# Microcell_1_4.net
KiCad netlist of a schematic drawn in EAGLE
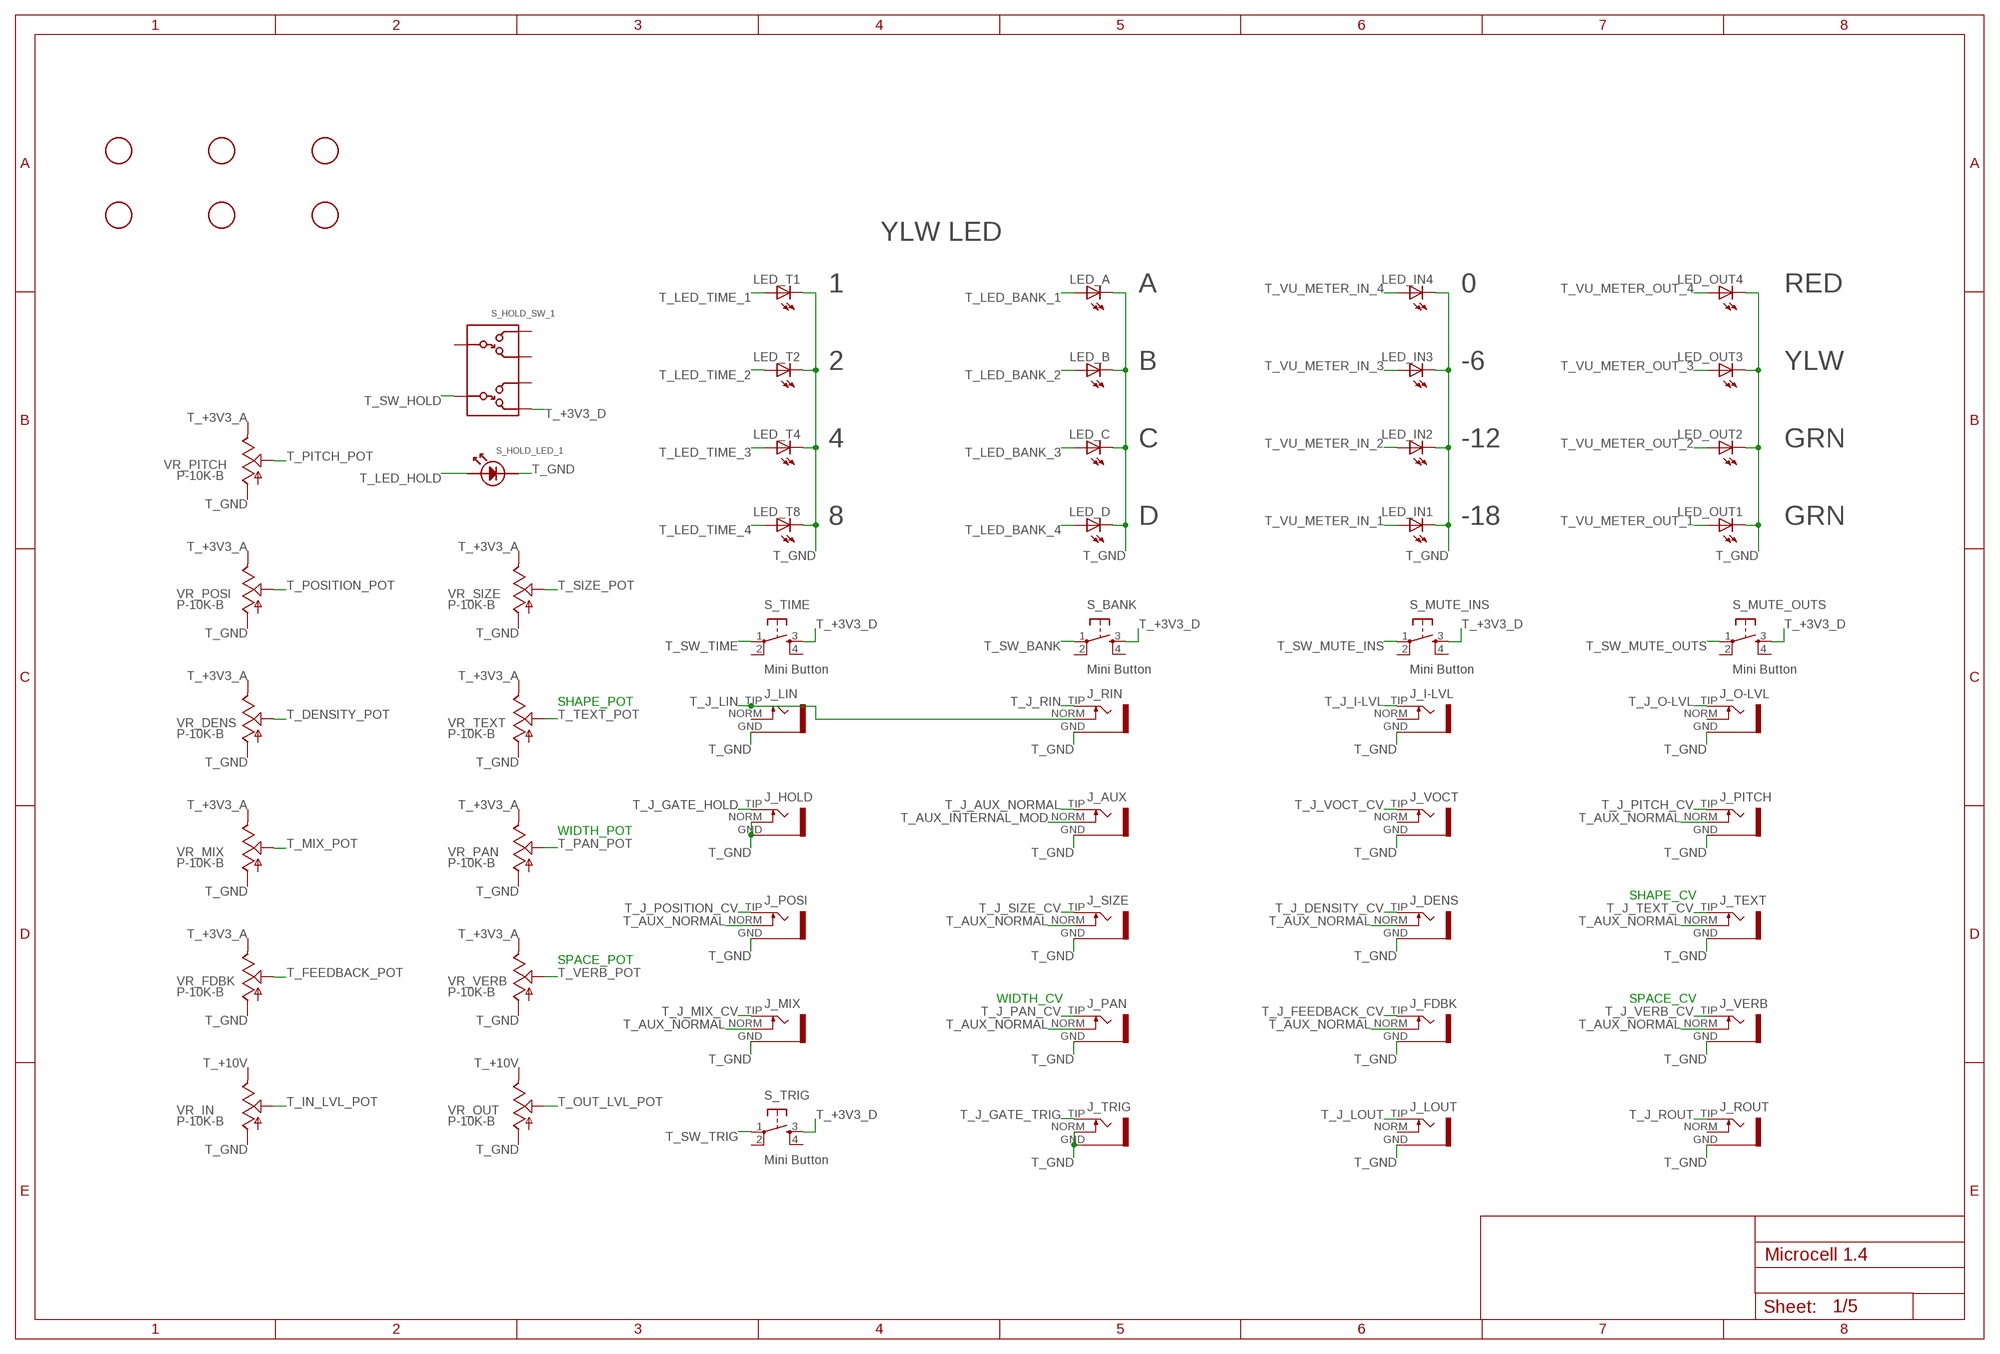
[diagram p0: schematic, sheet 1]
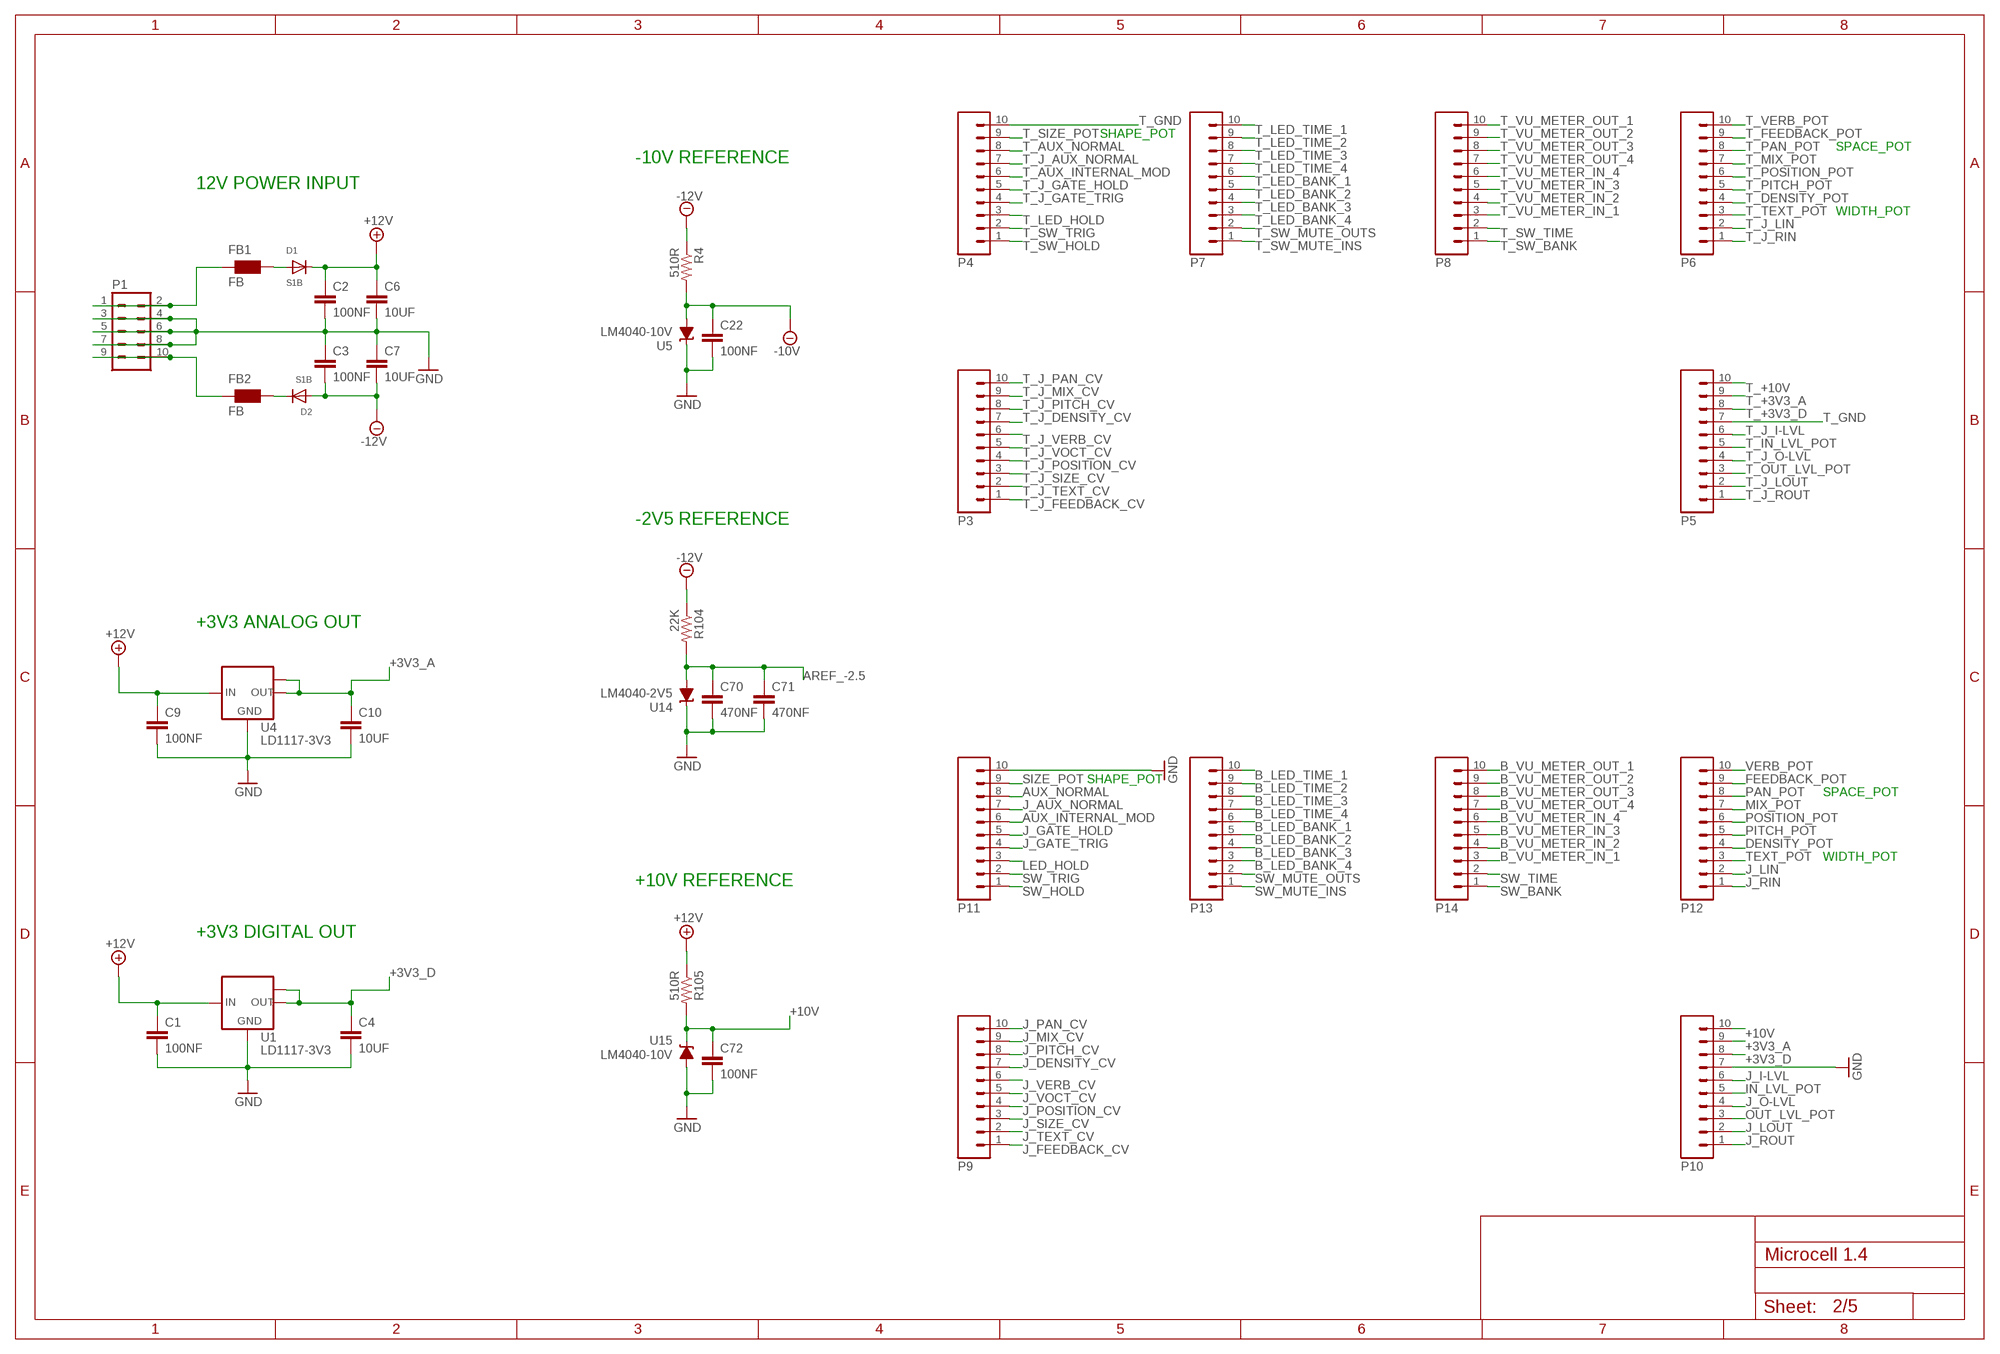
[diagram p1: schematic, sheet 2]
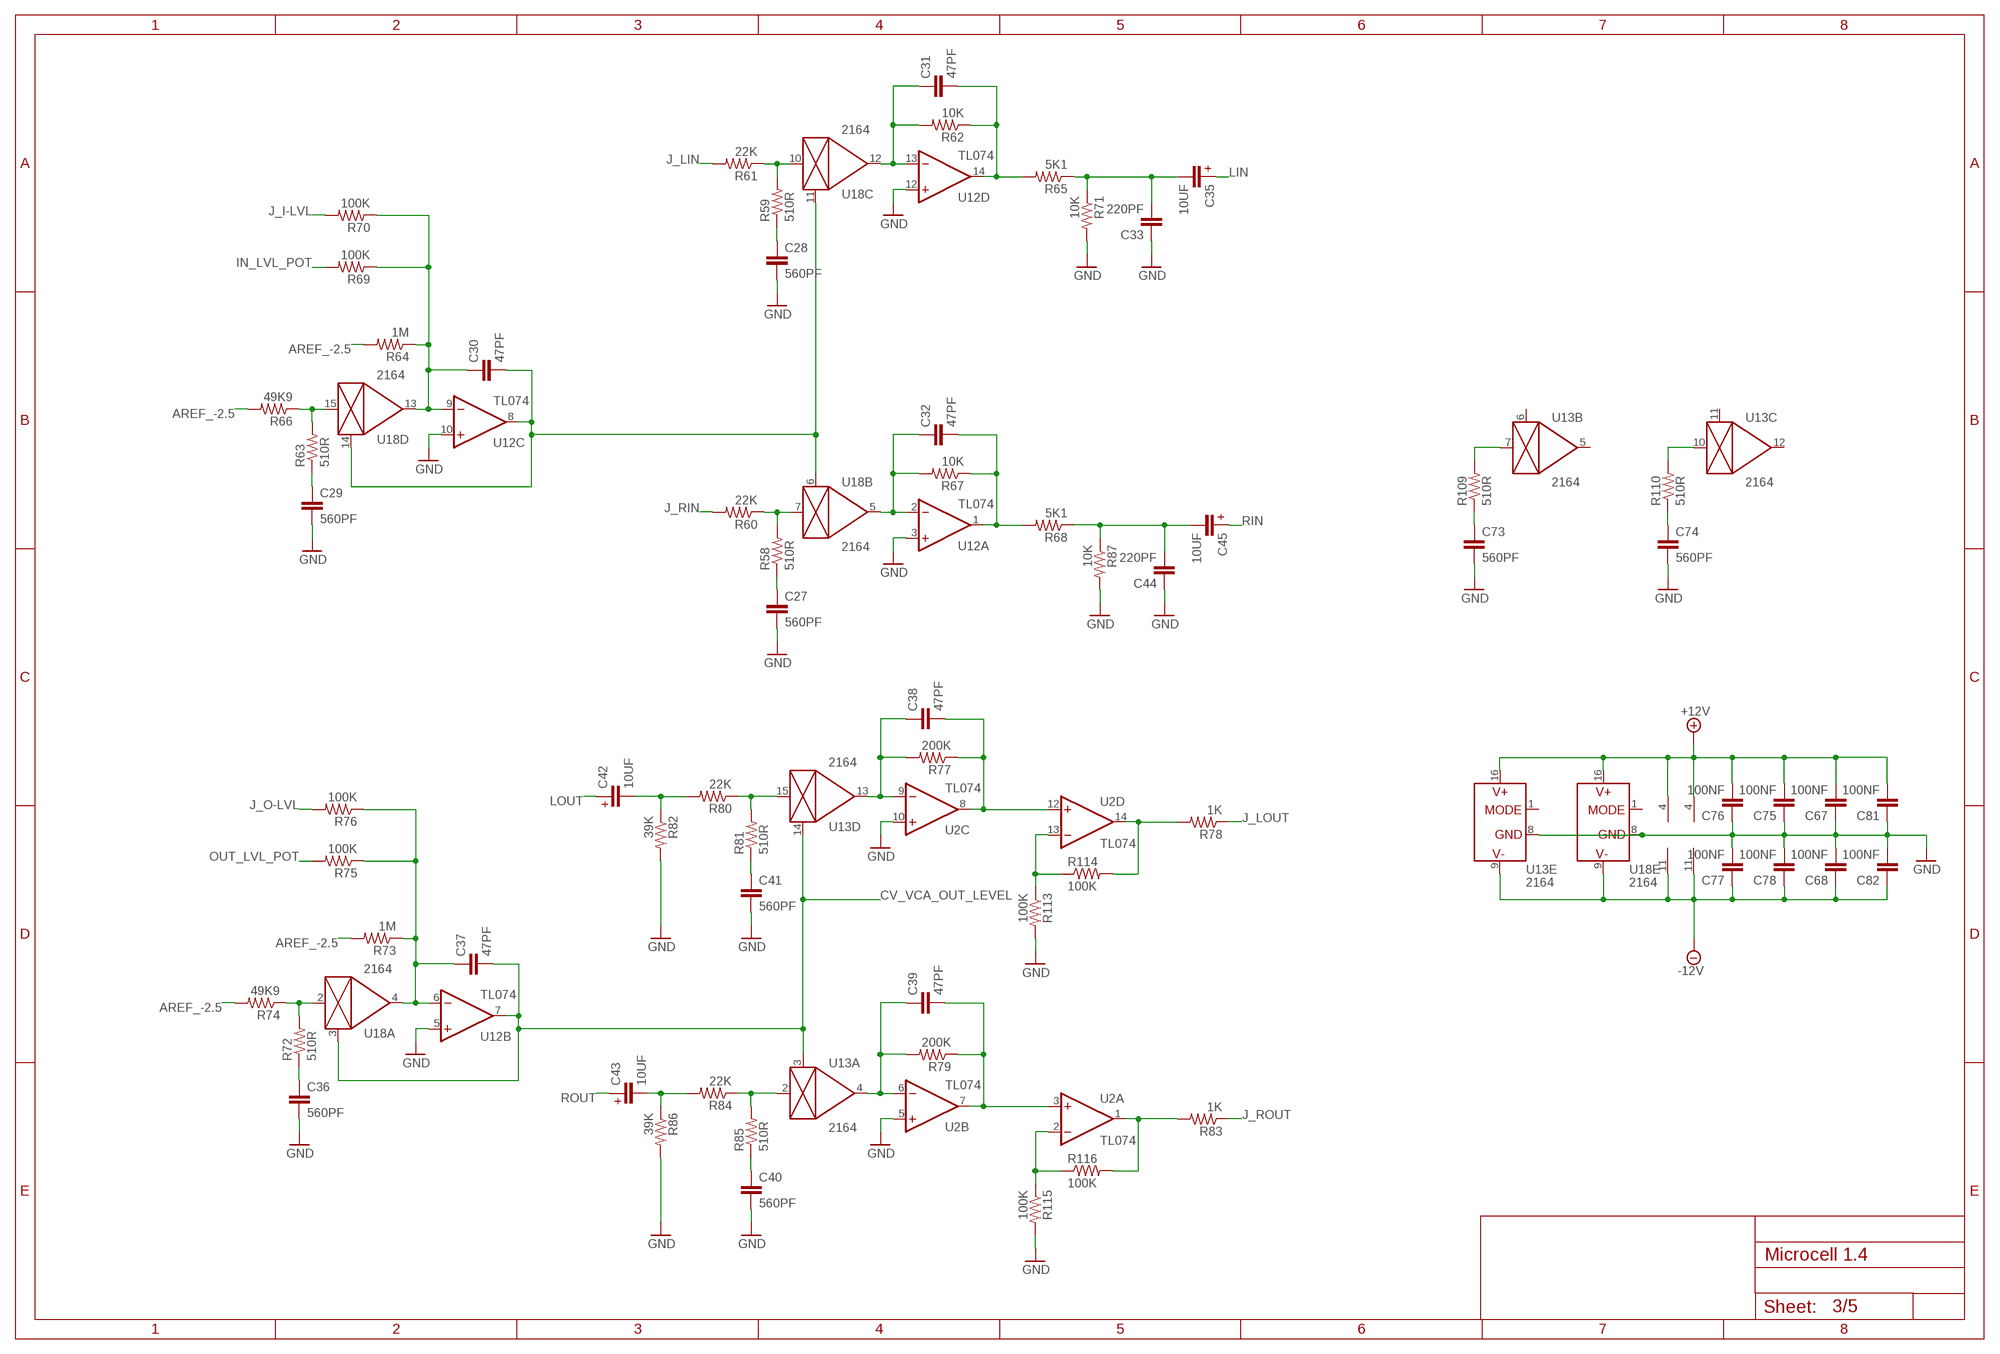
[diagram p2: schematic, sheet 3]
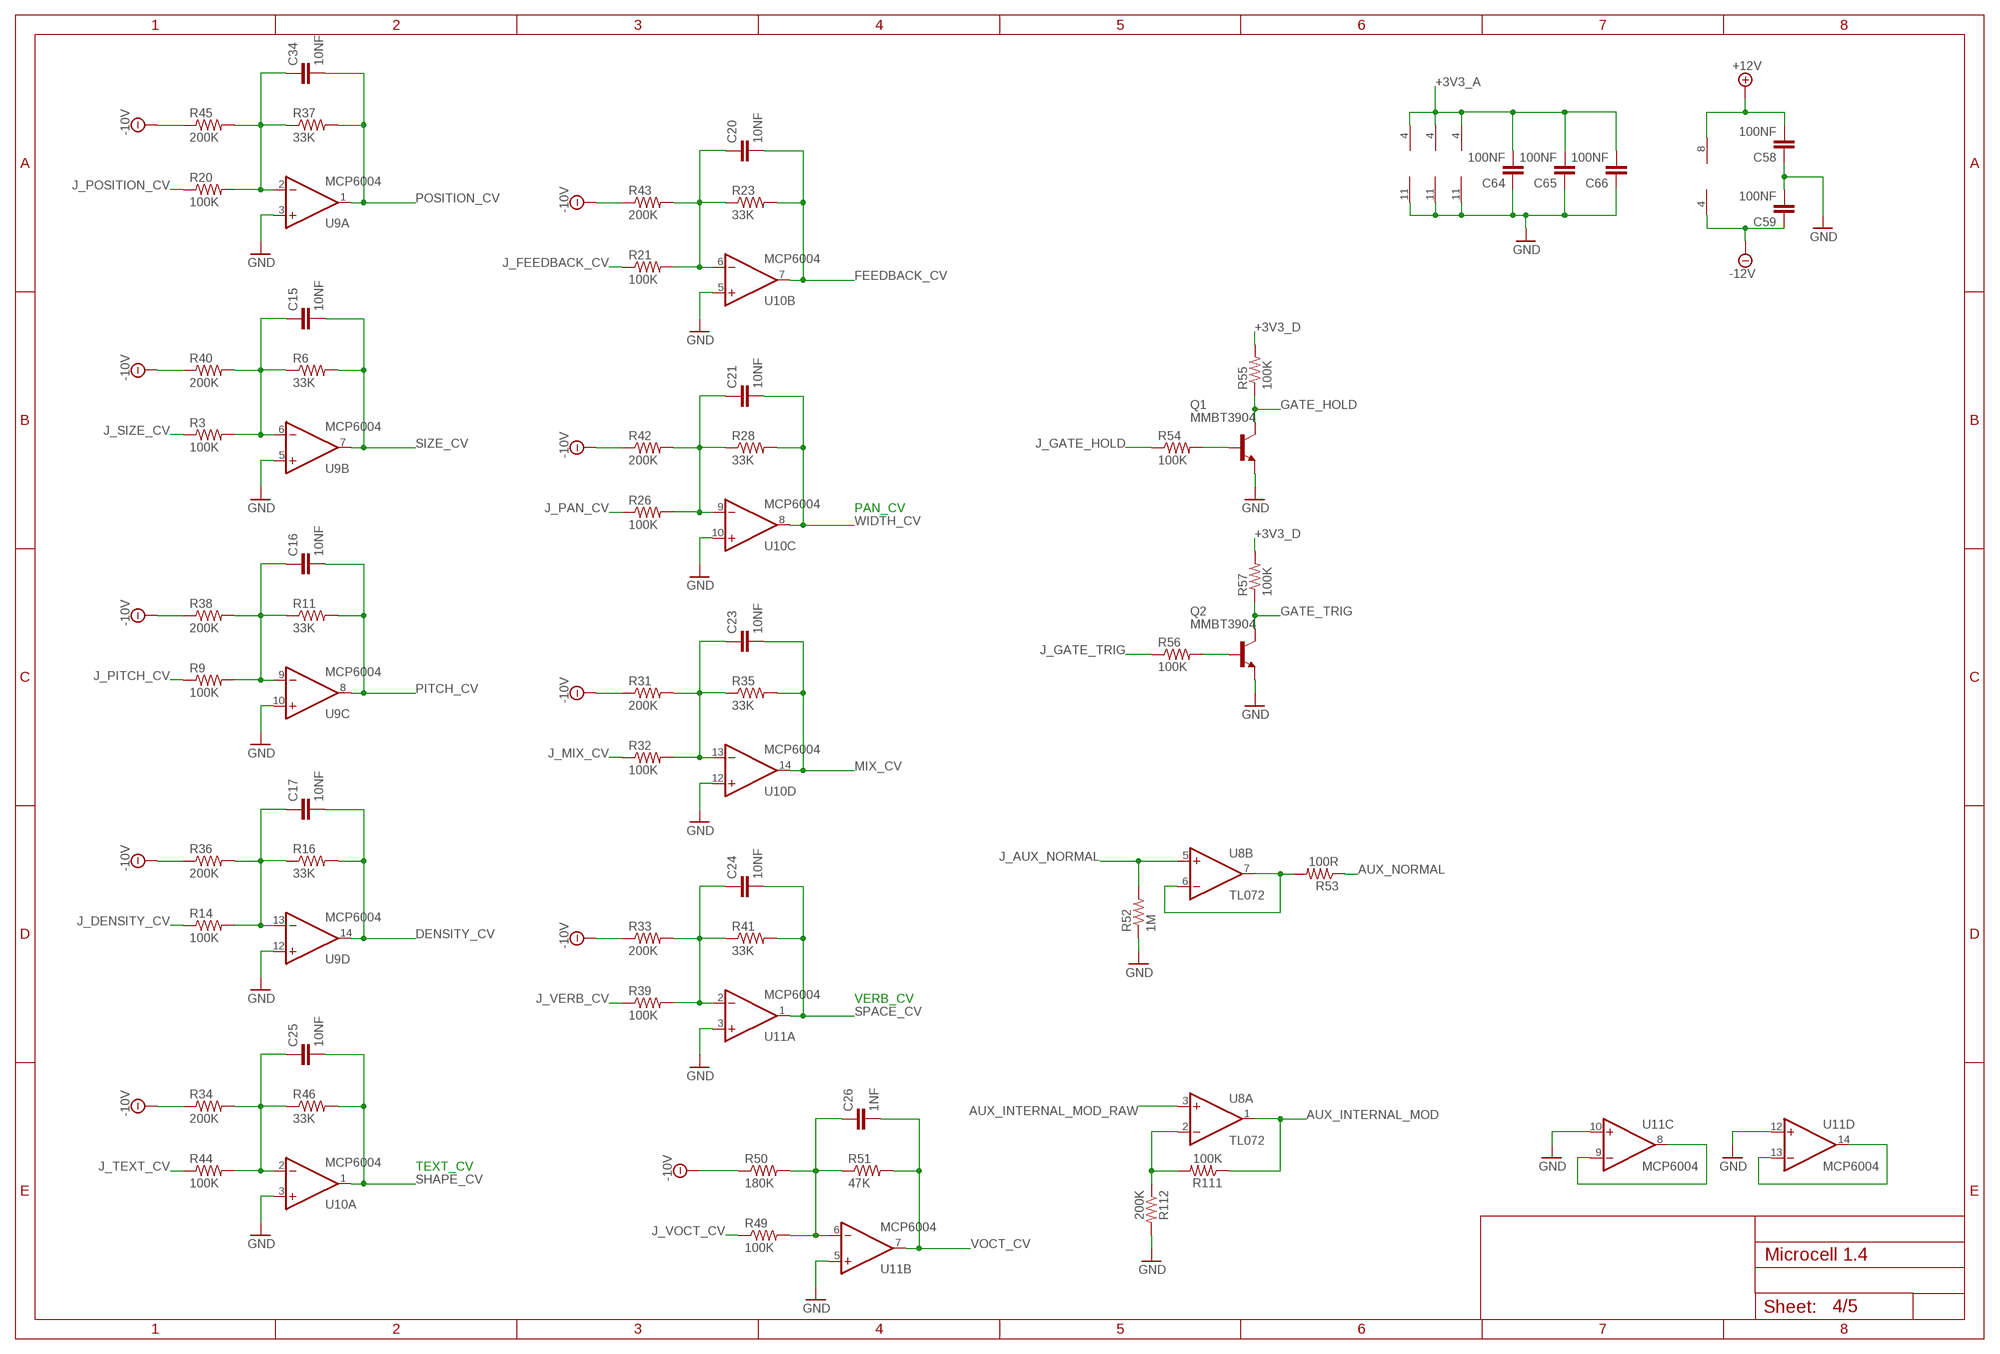
[diagram p3: schematic, sheet 4]
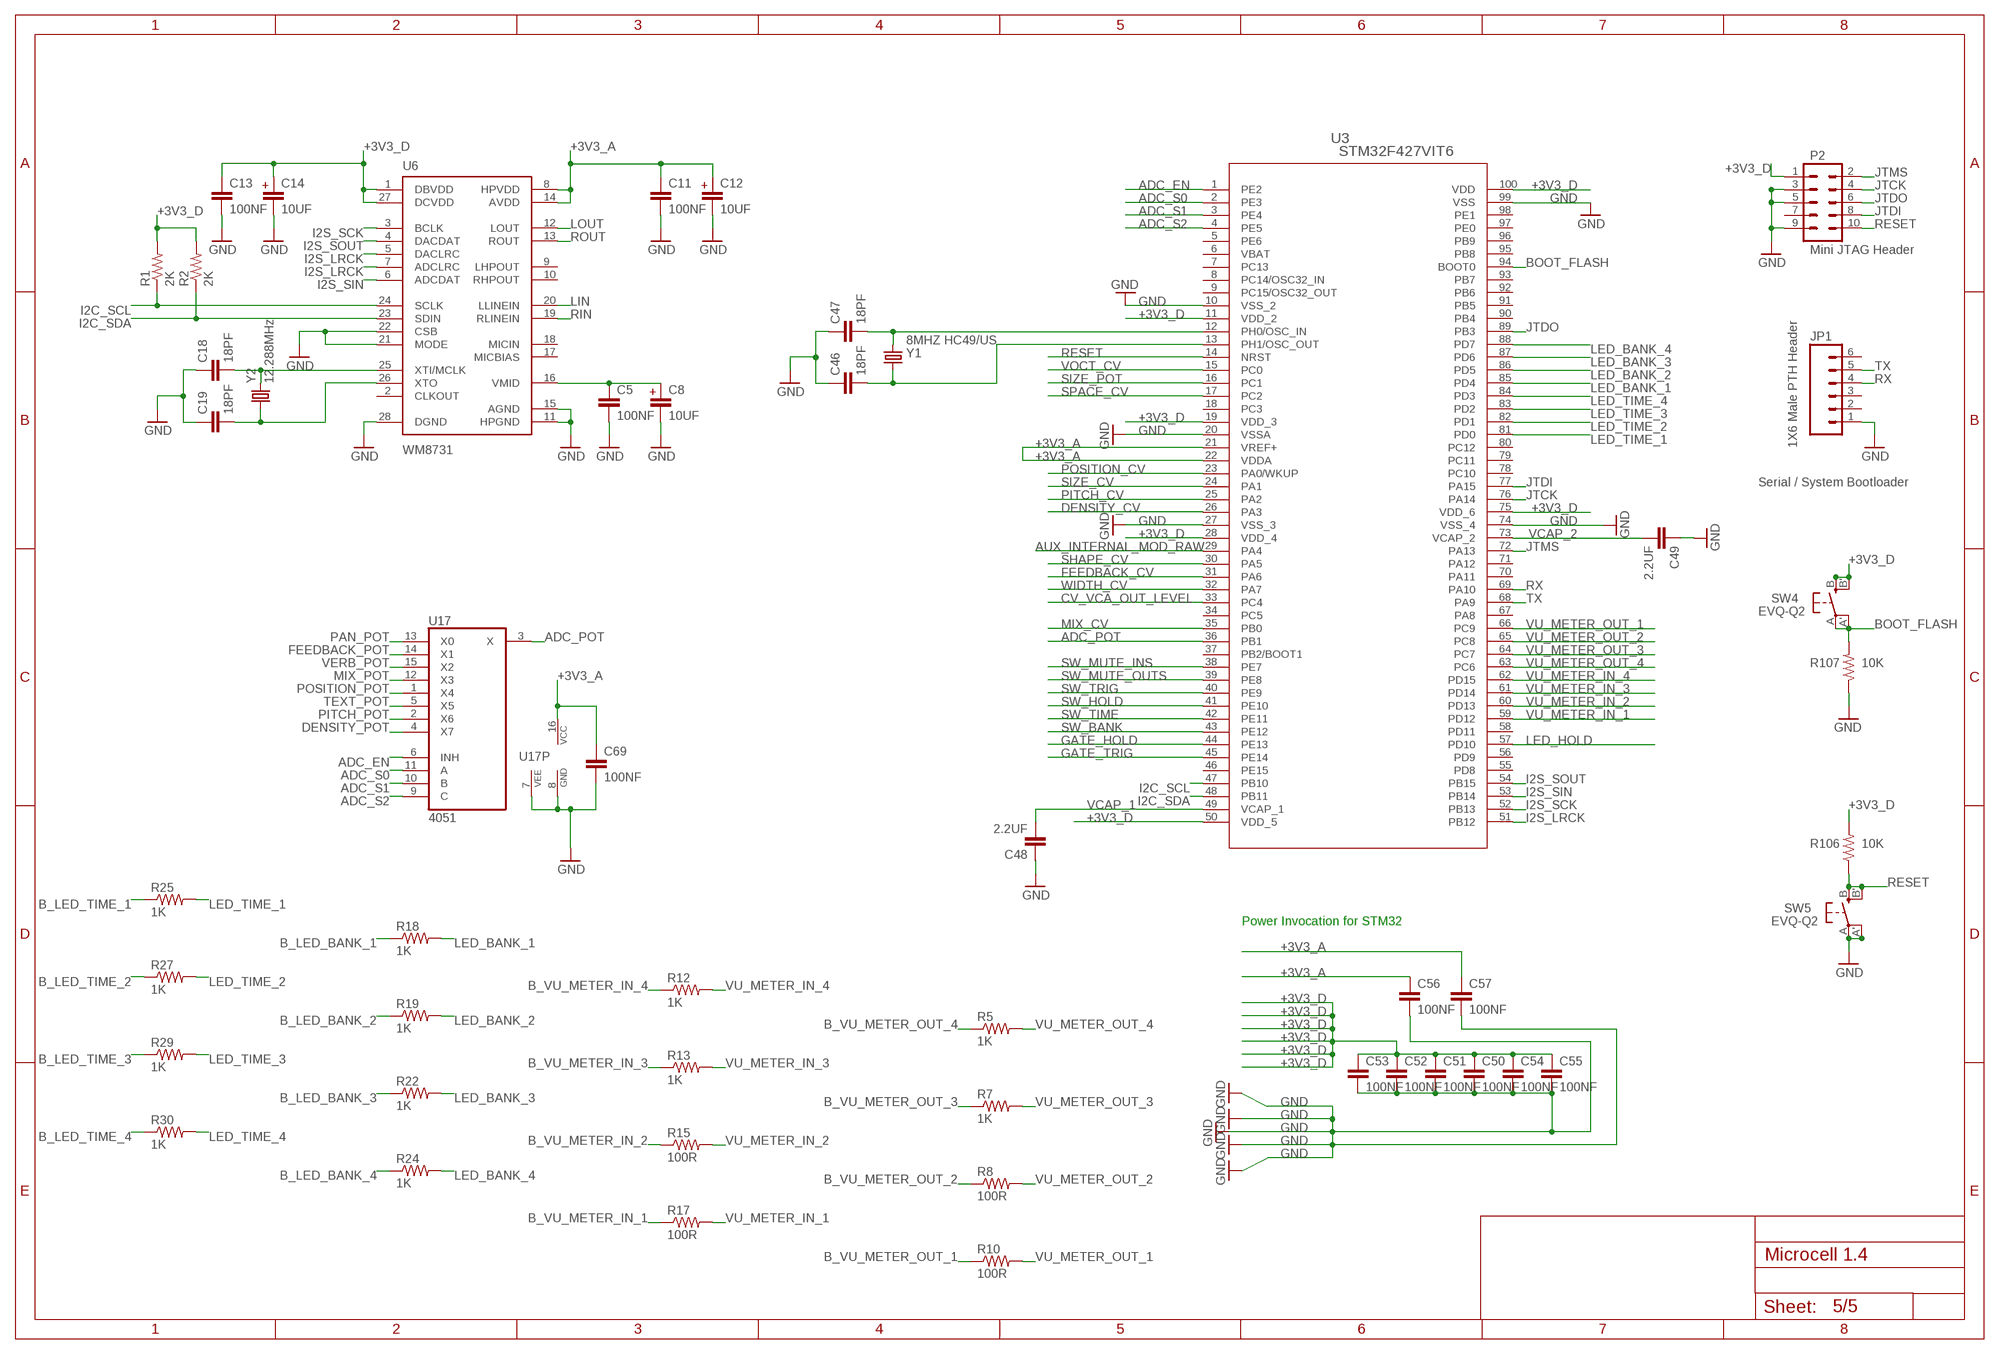
[diagram p4: schematic, sheet 5]

(export (version "E")
  (design (tool "Eeschema 10.0.6"))
  (components
    (comp (ref "C15")
      (value "10NF")
      (footprint "eagle-import:C0603")
      (libsource (lib "eagle-import") (part "C-EUC0603"))
    )
    (comp (ref "C16")
      (value "10NF")
      (footprint "eagle-import:C0603")
      (libsource (lib "eagle-import") (part "C-EUC0603"))
    )
    (comp (ref "C17")
      (value "10NF")
      (footprint "eagle-import:C0603")
      (libsource (lib "eagle-import") (part "C-EUC0603"))
    )
    (comp (ref "C20")
      (value "10NF")
      (footprint "eagle-import:C0603")
      (libsource (lib "eagle-import") (part "C-EUC0603"))
    )
    (comp (ref "C21")
      (value "10NF")
      (footprint "eagle-import:C0603")
      (libsource (lib "eagle-import") (part "C-EUC0603"))
    )
    (comp (ref "C23")
      (value "10NF")
      (footprint "eagle-import:C0603")
      (libsource (lib "eagle-import") (part "C-EUC0603"))
    )
    (comp (ref "C24")
      (value "10NF")
      (footprint "eagle-import:C0603")
      (libsource (lib "eagle-import") (part "C-EUC0603"))
    )
    (comp (ref "C25")
      (value "10NF")
      (footprint "eagle-import:C0603")
      (libsource (lib "eagle-import") (part "C-EUC0603"))
    )
    (comp (ref "C26")
      (value "1NF")
      (footprint "eagle-import:C0603")
      (libsource (lib "eagle-import") (part "C-EUC0603"))
    )
    (comp (ref "C34")
      (value "10NF")
      (footprint "eagle-import:C0603")
      (libsource (lib "eagle-import") (part "C-EUC0603"))
    )
    (comp (ref "C58")
      (value "100NF")
      (footprint "eagle-import:C0603")
      (libsource (lib "eagle-import") (part "C-EUC0603"))
    )
    (comp (ref "C59")
      (value "100NF")
      (footprint "eagle-import:C0603")
      (libsource (lib "eagle-import") (part "C-EUC0603"))
    )
    (comp (ref "C64")
      (value "100NF")
      (footprint "eagle-import:C0603")
      (libsource (lib "eagle-import") (part "C-EUC0603"))
    )
    (comp (ref "C65")
      (value "100NF")
      (footprint "eagle-import:C0603")
      (libsource (lib "eagle-import") (part "C-EUC0603"))
    )
    (comp (ref "C66")
      (value "100NF")
      (footprint "eagle-import:C0603")
      (libsource (lib "eagle-import") (part "C-EUC0603"))
    )
    (comp (ref "Q1")
      (value "MMBT3904")
      (footprint "eagle-import:SOT23-BEC")
      (libsource (lib "eagle-import") (part "-NPN-SOT23-BECMMBT3904LT1"))
    )
    (comp (ref "Q2")
      (value "MMBT3904")
      (footprint "eagle-import:SOT23-BEC")
      (libsource (lib "eagle-import") (part "-NPN-SOT23-BECMMBT3904LT1"))
    )
    (comp (ref "R3")
      (value "100K")
      (footprint "eagle-import:R0603")
      (libsource (lib "eagle-import") (part "R-US_R0603"))
    )
    (comp (ref "R6")
      (value "33K")
      (footprint "eagle-import:R0603")
      (libsource (lib "eagle-import") (part "R-US_R0603"))
    )
    (comp (ref "R9")
      (value "100K")
      (footprint "eagle-import:R0603")
      (libsource (lib "eagle-import") (part "R-US_R0603"))
    )
    (comp (ref "R11")
      (value "33K")
      (footprint "eagle-import:R0603")
      (libsource (lib "eagle-import") (part "R-US_R0603"))
    )
    (comp (ref "R14")
      (value "100K")
      (footprint "eagle-import:R0603")
      (libsource (lib "eagle-import") (part "R-US_R0603"))
    )
    (comp (ref "R16")
      (value "33K")
      (footprint "eagle-import:R0603")
      (libsource (lib "eagle-import") (part "R-US_R0603"))
    )
    (comp (ref "R20")
      (value "100K")
      (footprint "eagle-import:R0603")
      (libsource (lib "eagle-import") (part "R-US_R0603"))
    )
    (comp (ref "R21")
      (value "100K")
      (footprint "eagle-import:R0603")
      (libsource (lib "eagle-import") (part "R-US_R0603"))
    )
    (comp (ref "R23")
      (value "33K")
      (footprint "eagle-import:R0603")
      (libsource (lib "eagle-import") (part "R-US_R0603"))
    )
    (comp (ref "R26")
      (value "100K")
      (footprint "eagle-import:R0603")
      (libsource (lib "eagle-import") (part "R-US_R0603"))
    )
    (comp (ref "R28")
      (value "33K")
      (footprint "eagle-import:R0603")
      (libsource (lib "eagle-import") (part "R-US_R0603"))
    )
    (comp (ref "R31")
      (value "200K")
      (footprint "eagle-import:R0603")
      (libsource (lib "eagle-import") (part "R-US_R0603"))
    )
    (comp (ref "R32")
      (value "100K")
      (footprint "eagle-import:R0603")
      (libsource (lib "eagle-import") (part "R-US_R0603"))
    )
    (comp (ref "R33")
      (value "200K")
      (footprint "eagle-import:R0603")
      (libsource (lib "eagle-import") (part "R-US_R0603"))
    )
    (comp (ref "R34")
      (value "200K")
      (footprint "eagle-import:R0603")
      (libsource (lib "eagle-import") (part "R-US_R0603"))
    )
    (comp (ref "R35")
      (value "33K")
      (footprint "eagle-import:R0603")
      (libsource (lib "eagle-import") (part "R-US_R0603"))
    )
    (comp (ref "R36")
      (value "200K")
      (footprint "eagle-import:R0603")
      (libsource (lib "eagle-import") (part "R-US_R0603"))
    )
    (comp (ref "R37")
      (value "33K")
      (footprint "eagle-import:R0603")
      (libsource (lib "eagle-import") (part "R-US_R0603"))
    )
    (comp (ref "R38")
      (value "200K")
      (footprint "eagle-import:R0603")
      (libsource (lib "eagle-import") (part "R-US_R0603"))
    )
    (comp (ref "R39")
      (value "100K")
      (footprint "eagle-import:R0603")
      (libsource (lib "eagle-import") (part "R-US_R0603"))
    )
    (comp (ref "R40")
      (value "200K")
      (footprint "eagle-import:R0603")
      (libsource (lib "eagle-import") (part "R-US_R0603"))
    )
    (comp (ref "R41")
      (value "33K")
      (footprint "eagle-import:R0603")
      (libsource (lib "eagle-import") (part "R-US_R0603"))
    )
    (comp (ref "R42")
      (value "200K")
      (footprint "eagle-import:R0603")
      (libsource (lib "eagle-import") (part "R-US_R0603"))
    )
    (comp (ref "R43")
      (value "200K")
      (footprint "eagle-import:R0603")
      (libsource (lib "eagle-import") (part "R-US_R0603"))
    )
    (comp (ref "R44")
      (value "100K")
      (footprint "eagle-import:R0603")
      (libsource (lib "eagle-import") (part "R-US_R0603"))
    )
    (comp (ref "R45")
      (value "200K")
      (footprint "eagle-import:R0603")
      (libsource (lib "eagle-import") (part "R-US_R0603"))
    )
    (comp (ref "R46")
      (value "33K")
      (footprint "eagle-import:R0603")
      (libsource (lib "eagle-import") (part "R-US_R0603"))
    )
    (comp (ref "R49")
      (value "100K")
      (footprint "eagle-import:R0603")
      (libsource (lib "eagle-import") (part "R-US_R0603"))
    )
    (comp (ref "R50")
      (value "180K")
      (footprint "eagle-import:R0603")
      (libsource (lib "eagle-import") (part "R-US_R0603"))
    )
    (comp (ref "R51")
      (value "47K")
      (footprint "eagle-import:R0603")
      (libsource (lib "eagle-import") (part "R-US_R0603"))
    )
    (comp (ref "R52")
      (value "1M")
      (footprint "eagle-import:R0603")
      (libsource (lib "eagle-import") (part "R-US_R0603"))
    )
    (comp (ref "R53")
      (value "100R")
      (footprint "eagle-import:R0603")
      (libsource (lib "eagle-import") (part "R-US_R0603"))
    )
    (comp (ref "R54")
      (value "100K")
      (footprint "eagle-import:R0603")
      (libsource (lib "eagle-import") (part "R-US_R0603"))
    )
    (comp (ref "R55")
      (value "100K")
      (footprint "eagle-import:R0603")
      (libsource (lib "eagle-import") (part "R-US_R0603"))
    )
    (comp (ref "R56")
      (value "100K")
      (footprint "eagle-import:R0603")
      (libsource (lib "eagle-import") (part "R-US_R0603"))
    )
    (comp (ref "R57")
      (value "100K")
      (footprint "eagle-import:R0603")
      (libsource (lib "eagle-import") (part "R-US_R0603"))
    )
    (comp (ref "R111")
      (value "100K")
      (footprint "eagle-import:R0603")
      (libsource (lib "eagle-import") (part "R-US_R0603"))
    )
    (comp (ref "R112")
      (value "200K")
      (footprint "eagle-import:R0603")
      (libsource (lib "eagle-import") (part "R-US_R0603"))
    )
    (comp (ref "U8")
      (value "TL072")
      (footprint "eagle-import:SO-8")
      (fields (field (name "MPN") "TL072IDT"))
      (libsource (lib "eagle-import") (part "TL072_SO-8"))
    )
    (comp (ref "U9")
      (value "MCP6004")
      (footprint "eagle-import:SO-14")
      (fields (field (name "MPN") "MCP6004T-I/SL"))
      (libsource (lib "eagle-import") (part "MCP6004_SO-14"))
    )
    (comp (ref "U10")
      (value "MCP6004")
      (footprint "eagle-import:SO-14")
      (fields (field (name "MPN") "MCP6004T-I/SL"))
      (libsource (lib "eagle-import") (part "MCP6004_SO-14"))
    )
    (comp (ref "U11")
      (value "MCP6004")
      (footprint "eagle-import:SO-14")
      (fields (field (name "MPN") "MCP6004T-I/SL"))
      (libsource (lib "eagle-import") (part "MCP6004_SO-14"))
    )
    (comp (ref "C27")
      (value "560PF")
      (footprint "eagle-import:C0603")
      (libsource (lib "eagle-import") (part "C-EUC0603"))
    )
    (comp (ref "C28")
      (value "560PF")
      (footprint "eagle-import:C0603")
      (libsource (lib "eagle-import") (part "C-EUC0603"))
    )
    (comp (ref "C29")
      (value "560PF")
      (footprint "eagle-import:C0603")
      (libsource (lib "eagle-import") (part "C-EUC0603"))
    )
    (comp (ref "C30")
      (value "47PF")
      (footprint "eagle-import:C0603")
      (libsource (lib "eagle-import") (part "C-EUC0603"))
    )
    (comp (ref "C31")
      (value "47PF")
      (footprint "eagle-import:C0603")
      (libsource (lib "eagle-import") (part "C-EUC0603"))
    )
    (comp (ref "C32")
      (value "47PF")
      (footprint "eagle-import:C0603")
      (libsource (lib "eagle-import") (part "C-EUC0603"))
    )
    (comp (ref "C33")
      (value "220PF")
      (footprint "eagle-import:C0603")
      (libsource (lib "eagle-import") (part "C-EUC0603"))
    )
    (comp (ref "C35")
      (value "10UF")
      (footprint "eagle-import:EC-4X7")
      (libsource (lib "eagle-import") (part "C-EU-POL_4D"))
    )
    (comp (ref "C36")
      (value "560PF")
      (footprint "eagle-import:C0603")
      (libsource (lib "eagle-import") (part "C-EUC0603"))
    )
    (comp (ref "C37")
      (value "47PF")
      (footprint "eagle-import:C0603")
      (libsource (lib "eagle-import") (part "C-EUC0603"))
    )
    (comp (ref "C38")
      (value "47PF")
      (footprint "eagle-import:C0603")
      (libsource (lib "eagle-import") (part "C-EUC0603"))
    )
    (comp (ref "C39")
      (value "47PF")
      (footprint "eagle-import:C0603")
      (libsource (lib "eagle-import") (part "C-EUC0603"))
    )
    (comp (ref "C40")
      (value "560PF")
      (footprint "eagle-import:C0603")
      (libsource (lib "eagle-import") (part "C-EUC0603"))
    )
    (comp (ref "C41")
      (value "560PF")
      (footprint "eagle-import:C0603")
      (libsource (lib "eagle-import") (part "C-EUC0603"))
    )
    (comp (ref "C42")
      (value "10UF")
      (footprint "eagle-import:EC-4X7")
      (libsource (lib "eagle-import") (part "C-EU-POL_4D"))
    )
    (comp (ref "C43")
      (value "10UF")
      (footprint "eagle-import:EC-4X7")
      (libsource (lib "eagle-import") (part "C-EU-POL_4D"))
    )
    (comp (ref "C44")
      (value "220PF")
      (footprint "eagle-import:C0603")
      (libsource (lib "eagle-import") (part "C-EUC0603"))
    )
    (comp (ref "C45")
      (value "10UF")
      (footprint "eagle-import:EC-4X7")
      (libsource (lib "eagle-import") (part "C-EU-POL_4D"))
    )
    (comp (ref "C67")
      (value "100NF")
      (footprint "eagle-import:C0603")
      (libsource (lib "eagle-import") (part "C-EUC0603"))
    )
    (comp (ref "C68")
      (value "100NF")
      (footprint "eagle-import:C0603")
      (libsource (lib "eagle-import") (part "C-EUC0603"))
    )
    (comp (ref "C73")
      (value "560PF")
      (footprint "eagle-import:C0603")
      (libsource (lib "eagle-import") (part "C-EUC0603"))
    )
    (comp (ref "C74")
      (value "560PF")
      (footprint "eagle-import:C0603")
      (libsource (lib "eagle-import") (part "C-EUC0603"))
    )
    (comp (ref "C75")
      (value "100NF")
      (footprint "eagle-import:C0603")
      (libsource (lib "eagle-import") (part "C-EUC0603"))
    )
    (comp (ref "C76")
      (value "100NF")
      (footprint "eagle-import:C0603")
      (libsource (lib "eagle-import") (part "C-EUC0603"))
    )
    (comp (ref "C77")
      (value "100NF")
      (footprint "eagle-import:C0603")
      (libsource (lib "eagle-import") (part "C-EUC0603"))
    )
    (comp (ref "C78")
      (value "100NF")
      (footprint "eagle-import:C0603")
      (libsource (lib "eagle-import") (part "C-EUC0603"))
    )
    (comp (ref "C81")
      (value "100NF")
      (footprint "eagle-import:C0603")
      (libsource (lib "eagle-import") (part "C-EUC0603"))
    )
    (comp (ref "C82")
      (value "100NF")
      (footprint "eagle-import:C0603")
      (libsource (lib "eagle-import") (part "C-EUC0603"))
    )
    (comp (ref "R58")
      (value "510R")
      (footprint "eagle-import:R0603")
      (libsource (lib "eagle-import") (part "R-US_R0603"))
    )
    (comp (ref "R59")
      (value "510R")
      (footprint "eagle-import:R0603")
      (libsource (lib "eagle-import") (part "R-US_R0603"))
    )
    (comp (ref "R60")
      (value "22K")
      (footprint "eagle-import:R0603")
      (libsource (lib "eagle-import") (part "R-US_R0603"))
    )
    (comp (ref "R61")
      (value "22K")
      (footprint "eagle-import:R0603")
      (libsource (lib "eagle-import") (part "R-US_R0603"))
    )
    (comp (ref "R62")
      (value "10K")
      (footprint "eagle-import:R0603")
      (libsource (lib "eagle-import") (part "R-US_R0603"))
    )
    (comp (ref "R63")
      (value "510R")
      (footprint "eagle-import:R0603")
      (libsource (lib "eagle-import") (part "R-US_R0603"))
    )
    (comp (ref "R64")
      (value "1M")
      (footprint "eagle-import:R0603")
      (libsource (lib "eagle-import") (part "R-US_R0603"))
    )
    (comp (ref "R65")
      (value "5K1")
      (footprint "eagle-import:R0603")
      (libsource (lib "eagle-import") (part "R-US_R0603"))
    )
    (comp (ref "R66")
      (value "49K9")
      (footprint "eagle-import:R0603")
      (libsource (lib "eagle-import") (part "R-US_R0603"))
    )
    (comp (ref "R67")
      (value "10K")
      (footprint "eagle-import:R0603")
      (libsource (lib "eagle-import") (part "R-US_R0603"))
    )
    (comp (ref "R68")
      (value "5K1")
      (footprint "eagle-import:R0603")
      (libsource (lib "eagle-import") (part "R-US_R0603"))
    )
    (comp (ref "R69")
      (value "100K")
      (footprint "eagle-import:R0603")
      (libsource (lib "eagle-import") (part "R-US_R0603"))
    )
    (comp (ref "R70")
      (value "100K")
      (footprint "eagle-import:R0603")
      (libsource (lib "eagle-import") (part "R-US_R0603"))
    )
    (comp (ref "R71")
      (value "10K")
      (footprint "eagle-import:R0603")
      (libsource (lib "eagle-import") (part "R-US_R0603"))
    )
    (comp (ref "R72")
      (value "510R")
      (footprint "eagle-import:R0603")
      (libsource (lib "eagle-import") (part "R-US_R0603"))
    )
    (comp (ref "R73")
      (value "1M")
      (footprint "eagle-import:R0603")
      (libsource (lib "eagle-import") (part "R-US_R0603"))
    )
    (comp (ref "R74")
      (value "49K9")
      (footprint "eagle-import:R0603")
      (libsource (lib "eagle-import") (part "R-US_R0603"))
    )
    (comp (ref "R75")
      (value "100K")
      (footprint "eagle-import:R0603")
      (libsource (lib "eagle-import") (part "R-US_R0603"))
    )
    (comp (ref "R76")
      (value "100K")
      (footprint "eagle-import:R0603")
      (libsource (lib "eagle-import") (part "R-US_R0603"))
    )
    (comp (ref "R77")
      (value "200K")
      (footprint "eagle-import:R0603")
      (libsource (lib "eagle-import") (part "R-US_R0603"))
    )
    (comp (ref "R78")
      (value "1K")
      (footprint "eagle-import:R0603")
      (libsource (lib "eagle-import") (part "R-US_R0603"))
    )
    (comp (ref "R79")
      (value "200K")
      (footprint "eagle-import:R0603")
      (libsource (lib "eagle-import") (part "R-US_R0603"))
    )
    (comp (ref "R80")
      (value "22K")
      (footprint "eagle-import:R0603")
      (libsource (lib "eagle-import") (part "R-US_R0603"))
    )
    (comp (ref "R81")
      (value "510R")
      (footprint "eagle-import:R0603")
      (libsource (lib "eagle-import") (part "R-US_R0603"))
    )
    (comp (ref "R82")
      (value "39K")
      (footprint "eagle-import:R0603")
      (libsource (lib "eagle-import") (part "R-US_R0603"))
    )
    (comp (ref "R83")
      (value "1K")
      (footprint "eagle-import:R0603")
      (libsource (lib "eagle-import") (part "R-US_R0603"))
    )
    (comp (ref "R84")
      (value "22K")
      (footprint "eagle-import:R0603")
      (libsource (lib "eagle-import") (part "R-US_R0603"))
    )
    (comp (ref "R85")
      (value "510R")
      (footprint "eagle-import:R0603")
      (libsource (lib "eagle-import") (part "R-US_R0603"))
    )
    (comp (ref "R86")
      (value "39K")
      (footprint "eagle-import:R0603")
      (libsource (lib "eagle-import") (part "R-US_R0603"))
    )
    (comp (ref "R87")
      (value "10K")
      (footprint "eagle-import:R0603")
      (libsource (lib "eagle-import") (part "R-US_R0603"))
    )
    (comp (ref "R109")
      (value "510R")
      (footprint "eagle-import:R0603")
      (libsource (lib "eagle-import") (part "R-US_R0603"))
    )
    (comp (ref "R110")
      (value "510R")
      (footprint "eagle-import:R0603")
      (libsource (lib "eagle-import") (part "R-US_R0603"))
    )
    (comp (ref "R113")
      (value "100K")
      (footprint "eagle-import:R0603")
      (libsource (lib "eagle-import") (part "R-US_R0603"))
    )
    (comp (ref "R114")
      (value "100K")
      (footprint "eagle-import:R0603")
      (libsource (lib "eagle-import") (part "R-US_R0603"))
    )
    (comp (ref "R115")
      (value "100K")
      (footprint "eagle-import:R0603")
      (libsource (lib "eagle-import") (part "R-US_R0603"))
    )
    (comp (ref "R116")
      (value "100K")
      (footprint "eagle-import:R0603")
      (libsource (lib "eagle-import") (part "R-US_R0603"))
    )
    (comp (ref "U2")
      (value "TL074")
      (footprint "eagle-import:SO-14")
      (fields (field (name "MPN") "TL074CDR"))
      (libsource (lib "eagle-import") (part "TL074_SO-14"))
    )
    (comp (ref "U12")
      (value "TL074")
      (footprint "eagle-import:SO-14")
      (fields (field (name "MPN") "TL074CDR"))
      (libsource (lib "eagle-import") (part "TL074_SO-14"))
    )
    (comp (ref "U13")
      (value "2164")
      (footprint "eagle-import:SO-16")
      (fields (field (name "MPN") "SSI2164S-RT"))
      (libsource (lib "eagle-import") (part "SSI2164"))
    )
    (comp (ref "U18")
      (value "2164")
      (footprint "eagle-import:SO-16")
      (fields (field (name "MPN") "SSI2164S-RT"))
      (libsource (lib "eagle-import") (part "SSI2164"))
    )
    (comp (ref "C5")
      (value "100NF")
      (footprint "eagle-import:C0603")
      (libsource (lib "eagle-import") (part "C-EUC0603"))
    )
    (comp (ref "C8")
      (value "10UF")
      (footprint "eagle-import:EC-4X7")
      (libsource (lib "eagle-import") (part "C-EU-POL_4D"))
    )
    (comp (ref "C11")
      (value "100NF")
      (footprint "eagle-import:C0603")
      (libsource (lib "eagle-import") (part "C-EUC0603"))
    )
    (comp (ref "C12")
      (value "10UF")
      (footprint "eagle-import:EC-4X7")
      (libsource (lib "eagle-import") (part "C-EU-POL_4D"))
    )
    (comp (ref "C13")
      (value "100NF")
      (footprint "eagle-import:C0603")
      (libsource (lib "eagle-import") (part "C-EUC0603"))
    )
    (comp (ref "C14")
      (value "10UF")
      (footprint "eagle-import:EC-4X7")
      (libsource (lib "eagle-import") (part "C-EU-POL_4D"))
    )
    (comp (ref "C18")
      (value "18PF")
      (footprint "eagle-import:C0603")
      (libsource (lib "eagle-import") (part "C-EUC0603"))
    )
    (comp (ref "C19")
      (value "18PF")
      (footprint "eagle-import:C0603")
      (libsource (lib "eagle-import") (part "C-EUC0603"))
    )
    (comp (ref "C46")
      (value "18PF")
      (footprint "eagle-import:C0603")
      (libsource (lib "eagle-import") (part "C-EUC0603"))
    )
    (comp (ref "C47")
      (value "18PF")
      (footprint "eagle-import:C0603")
      (libsource (lib "eagle-import") (part "C-EUC0603"))
    )
    (comp (ref "C48")
      (value "2.2UF")
      (footprint "eagle-import:C0603")
      (libsource (lib "eagle-import") (part "C-EUC0603"))
    )
    (comp (ref "C49")
      (value "2.2UF")
      (footprint "eagle-import:C0603")
      (libsource (lib "eagle-import") (part "C-EUC0603"))
    )
    (comp (ref "C50")
      (value "100NF")
      (footprint "eagle-import:C0603")
      (libsource (lib "eagle-import") (part "C-EUC0603"))
    )
    (comp (ref "C51")
      (value "100NF")
      (footprint "eagle-import:C0603")
      (libsource (lib "eagle-import") (part "C-EUC0603"))
    )
    (comp (ref "C52")
      (value "100NF")
      (footprint "eagle-import:C0603")
      (libsource (lib "eagle-import") (part "C-EUC0603"))
    )
    (comp (ref "C53")
      (value "100NF")
      (footprint "eagle-import:C0603")
      (libsource (lib "eagle-import") (part "C-EUC0603"))
    )
    (comp (ref "C54")
      (value "100NF")
      (footprint "eagle-import:C0603")
      (libsource (lib "eagle-import") (part "C-EUC0603"))
    )
    (comp (ref "C55")
      (value "100NF")
      (footprint "eagle-import:C0603")
      (libsource (lib "eagle-import") (part "C-EUC0603"))
    )
    (comp (ref "C56")
      (value "100NF")
      (footprint "eagle-import:C0603")
      (libsource (lib "eagle-import") (part "C-EUC0603"))
    )
    (comp (ref "C57")
      (value "100NF")
      (footprint "eagle-import:C0603")
      (libsource (lib "eagle-import") (part "C-EUC0603"))
    )
    (comp (ref "C69")
      (value "100NF")
      (footprint "eagle-import:C0603")
      (libsource (lib "eagle-import") (part "C-EUC0603"))
    )
    (comp (ref "JP1")
      (value "1X6 Male PTH Header")
      (footprint "eagle-import:1X06")
      (libsource (lib "eagle-import") (part "M06SIP"))
    )
    (comp (ref "P2")
      (value "Mini JTAG Header")
      (footprint "eagle-import:2X5-1.27")
      (libsource (lib "eagle-import") (part "M05X2MINIJTAG"))
    )
    (comp (ref "R1")
      (value "2K")
      (footprint "eagle-import:R0603")
      (libsource (lib "eagle-import") (part "R-US_R0603"))
    )
    (comp (ref "R2")
      (value "2K")
      (footprint "eagle-import:R0603")
      (libsource (lib "eagle-import") (part "R-US_R0603"))
    )
    (comp (ref "R5")
      (value "1K")
      (footprint "eagle-import:R0603")
      (libsource (lib "eagle-import") (part "R-US_R0603"))
    )
    (comp (ref "R7")
      (value "1K")
      (footprint "eagle-import:R0603")
      (libsource (lib "eagle-import") (part "R-US_R0603"))
    )
    (comp (ref "R8")
      (value "100R")
      (footprint "eagle-import:R0603")
      (libsource (lib "eagle-import") (part "R-US_R0603"))
    )
    (comp (ref "R10")
      (value "100R")
      (footprint "eagle-import:R0603")
      (libsource (lib "eagle-import") (part "R-US_R0603"))
    )
    (comp (ref "R12")
      (value "1K")
      (footprint "eagle-import:R0603")
      (libsource (lib "eagle-import") (part "R-US_R0603"))
    )
    (comp (ref "R13")
      (value "1K")
      (footprint "eagle-import:R0603")
      (libsource (lib "eagle-import") (part "R-US_R0603"))
    )
    (comp (ref "R15")
      (value "100R")
      (footprint "eagle-import:R0603")
      (libsource (lib "eagle-import") (part "R-US_R0603"))
    )
    (comp (ref "R17")
      (value "100R")
      (footprint "eagle-import:R0603")
      (libsource (lib "eagle-import") (part "R-US_R0603"))
    )
    (comp (ref "R18")
      (value "1K")
      (footprint "eagle-import:R0603")
      (libsource (lib "eagle-import") (part "R-US_R0603"))
    )
    (comp (ref "R19")
      (value "1K")
      (footprint "eagle-import:R0603")
      (libsource (lib "eagle-import") (part "R-US_R0603"))
    )
    (comp (ref "R22")
      (value "1K")
      (footprint "eagle-import:R0603")
      (libsource (lib "eagle-import") (part "R-US_R0603"))
    )
    (comp (ref "R24")
      (value "1K")
      (footprint "eagle-import:R0603")
      (libsource (lib "eagle-import") (part "R-US_R0603"))
    )
    (comp (ref "R25")
      (value "1K")
      (footprint "eagle-import:R0603")
      (libsource (lib "eagle-import") (part "R-US_R0603"))
    )
    (comp (ref "R27")
      (value "1K")
      (footprint "eagle-import:R0603")
      (libsource (lib "eagle-import") (part "R-US_R0603"))
    )
    (comp (ref "R29")
      (value "1K")
      (footprint "eagle-import:R0603")
      (libsource (lib "eagle-import") (part "R-US_R0603"))
    )
    (comp (ref "R30")
      (value "1K")
      (footprint "eagle-import:R0603")
      (libsource (lib "eagle-import") (part "R-US_R0603"))
    )
    (comp (ref "R106")
      (value "10K")
      (footprint "eagle-import:R0603")
      (libsource (lib "eagle-import") (part "R-US_R0603"))
    )
    (comp (ref "R107")
      (value "10K")
      (footprint "eagle-import:R0603")
      (libsource (lib "eagle-import") (part "R-US_R0603"))
    )
    (comp (ref "SW4")
      (value "EVQ-Q2")
      (footprint "eagle-import:EVQ-Q2")
      (libsource (lib "eagle-import") (part "EVQQ2"))
    )
    (comp (ref "SW5")
      (value "EVQ-Q2")
      (footprint "eagle-import:EVQ-Q2")
      (libsource (lib "eagle-import") (part "EVQQ2"))
    )
    (comp (ref "U3")
      (value "STM32F427VIT6")
      (footprint "eagle-import:LQFP100-14X14MM")
      (fields (field (name "MANUFACTURER_PART_NUMBER") "stm32f4xxv2") (field (name "MPN") "empty"))
      (libsource (lib "eagle-import") (part "STM32F4XXV2"))
    )
    (comp (ref "U6")
      (value "WM8731")
      (footprint "eagle-import:SSOP-28")
      (fields (field (name "MPN") "WM8731SEDS/RV"))
      (libsource (lib "eagle-import") (part "WM8731"))
    )
    (comp (ref "U17")
      (value "4051")
      (footprint "eagle-import:SO-16")
      (libsource (lib "eagle-import") (part "4051_MUX"))
    )
    (comp (ref "Y1")
      (value "8MHZ HC49/US")
      (footprint "eagle-import:HC49UP")
      (libsource (lib "eagle-import") (part "CRYSTALHC49UP"))
    )
    (comp (ref "Y2")
      (value "12.288MHz")
      (footprint "eagle-import:HC49UP")
      (libsource (lib "eagle-import") (part "CRYSTALHC49UP"))
    )
    (comp (ref "FD1")
      (value "FIDUCIAL")
      (footprint "eagle-import:FIDUCIAL_1MM")
      (libsource (lib "eagle-import") (part "FIDUCIAL"))
    )
    (comp (ref "FD2")
      (value "FIDUCIAL")
      (footprint "eagle-import:FIDUCIAL_1MM")
      (libsource (lib "eagle-import") (part "FIDUCIAL"))
    )
    (comp (ref "FD3")
      (value "FIDUCIAL")
      (footprint "eagle-import:FIDUCIAL_1MM")
      (libsource (lib "eagle-import") (part "FIDUCIAL"))
    )
    (comp (ref "FD4")
      (value "FIDUCIAL")
      (footprint "eagle-import:FIDUCIAL_1MM")
      (libsource (lib "eagle-import") (part "FIDUCIAL"))
    )
    (comp (ref "FD5")
      (value "FIDUCIAL")
      (footprint "eagle-import:FIDUCIAL_1MM")
      (libsource (lib "eagle-import") (part "FIDUCIAL"))
    )
    (comp (ref "FD6")
      (value "FIDUCIAL")
      (footprint "eagle-import:FIDUCIAL_1MM")
      (libsource (lib "eagle-import") (part "FIDUCIAL"))
    )
    (comp (ref "J_AUX")
      (value "Eurorack Jack")
      (footprint "eagle-import:S_JACK_SMALL_SILK")
      (libsource (lib "eagle-import") (part "EURO_JACKS_SMALL_SILK"))
    )
    (comp (ref "J_DENS")
      (value "Eurorack Jack")
      (footprint "eagle-import:S_JACK_SILK")
      (libsource (lib "eagle-import") (part "EURO_JACKS_SILK"))
    )
    (comp (ref "J_FDBK")
      (value "Eurorack Jack")
      (footprint "eagle-import:S_JACK_SILK")
      (libsource (lib "eagle-import") (part "EURO_JACKS_SILK"))
    )
    (comp (ref "J_HOLD")
      (value "Eurorack Jack")
      (footprint "eagle-import:S_JACK_SMALL_SILK")
      (libsource (lib "eagle-import") (part "EURO_JACKS_SMALL_SILK"))
    )
    (comp (ref "J_I-LVL")
      (value "Eurorack Jack")
      (footprint "eagle-import:S_JACK_SILK")
      (libsource (lib "eagle-import") (part "EURO_JACKS_SILK"))
    )
    (comp (ref "J_LIN")
      (value "Eurorack Jack")
      (footprint "eagle-import:S_JACK_SILK")
      (libsource (lib "eagle-import") (part "EURO_JACKS_SILK"))
    )
    (comp (ref "J_LOUT")
      (value "Eurorack Jack")
      (footprint "eagle-import:S_JACK_SILK")
      (libsource (lib "eagle-import") (part "EURO_JACKS_SILK"))
    )
    (comp (ref "J_MIX")
      (value "Eurorack Jack")
      (footprint "eagle-import:S_JACK_SILK")
      (libsource (lib "eagle-import") (part "EURO_JACKS_SILK"))
    )
    (comp (ref "J_O-LVL")
      (value "Eurorack Jack")
      (footprint "eagle-import:S_JACK_SILK")
      (libsource (lib "eagle-import") (part "EURO_JACKS_SILK"))
    )
    (comp (ref "J_PAN")
      (value "Eurorack Jack")
      (footprint "eagle-import:S_JACK_SILK")
      (libsource (lib "eagle-import") (part "EURO_JACKS_SILK"))
    )
    (comp (ref "J_PITCH")
      (value "Eurorack Jack")
      (footprint "eagle-import:S_JACK_SILK")
      (libsource (lib "eagle-import") (part "EURO_JACKS_SILK"))
    )
    (comp (ref "J_POSI")
      (value "Eurorack Jack")
      (footprint "eagle-import:S_JACK_SILK")
      (libsource (lib "eagle-import") (part "EURO_JACKS_SILK"))
    )
    (comp (ref "J_RIN")
      (value "Eurorack Jack")
      (footprint "eagle-import:S_JACK_SILK")
      (libsource (lib "eagle-import") (part "EURO_JACKS_SILK"))
    )
    (comp (ref "J_ROUT")
      (value "Eurorack Jack")
      (footprint "eagle-import:S_JACK_SILK")
      (libsource (lib "eagle-import") (part "EURO_JACKS_SILK"))
    )
    (comp (ref "J_SIZE")
      (value "Eurorack Jack")
      (footprint "eagle-import:S_JACK_SILK")
      (libsource (lib "eagle-import") (part "EURO_JACKS_SILK"))
    )
    (comp (ref "J_TEXT")
      (value "Eurorack Jack")
      (footprint "eagle-import:S_JACK_SILK")
      (libsource (lib "eagle-import") (part "EURO_JACKS_SILK"))
    )
    (comp (ref "J_TRIG")
      (value "Eurorack Jack")
      (footprint "eagle-import:S_JACK_SMALL_SILK")
      (libsource (lib "eagle-import") (part "EURO_JACKS_SMALL_SILK"))
    )
    (comp (ref "J_VERB")
      (value "Eurorack Jack")
      (footprint "eagle-import:S_JACK_SILK")
      (libsource (lib "eagle-import") (part "EURO_JACKS_SILK"))
    )
    (comp (ref "J_VOCT")
      (value "Eurorack Jack")
      (footprint "eagle-import:S_JACK_SILK")
      (libsource (lib "eagle-import") (part "EURO_JACKS_SILK"))
    )
    (comp (ref "LED_A")
      (value "3mm Yellow Diffused")
      (footprint "eagle-import:LED_SILK")
      (libsource (lib "eagle-import") (part "LED_SILK"))
    )
    (comp (ref "LED_B")
      (value "3mm Yellow Diffused")
      (footprint "eagle-import:LED_SILK")
      (libsource (lib "eagle-import") (part "LED_SILK"))
    )
    (comp (ref "LED_C")
      (value "3mm Yellow Diffused")
      (footprint "eagle-import:LED_SILK")
      (libsource (lib "eagle-import") (part "LED_SILK"))
    )
    (comp (ref "LED_D")
      (value "3mm Yellow Diffused")
      (footprint "eagle-import:LED_SILK")
      (libsource (lib "eagle-import") (part "LED_SILK"))
    )
    (comp (ref "LED_IN1")
      (value "3mm Green Diffused")
      (footprint "eagle-import:LED_SILK")
      (libsource (lib "eagle-import") (part "LED_SILK"))
    )
    (comp (ref "LED_IN2")
      (value "3mm Green Diffused")
      (footprint "eagle-import:LED_SILK")
      (libsource (lib "eagle-import") (part "LED_SILK"))
    )
    (comp (ref "LED_IN3")
      (value "3mm Yellow Diffused")
      (footprint "eagle-import:LED_SILK")
      (libsource (lib "eagle-import") (part "LED_SILK"))
    )
    (comp (ref "LED_IN4")
      (value "3mm Red Diffused")
      (footprint "eagle-import:LED_SILK")
      (libsource (lib "eagle-import") (part "LED_SILK"))
    )
    (comp (ref "LED_OUT1")
      (value "3mm Green Diffused")
      (footprint "eagle-import:LED_SILK")
      (libsource (lib "eagle-import") (part "LED_SILK"))
    )
    (comp (ref "LED_OUT2")
      (value "3mm Green Diffused")
      (footprint "eagle-import:LED_SILK")
      (libsource (lib "eagle-import") (part "LED_SILK"))
    )
    (comp (ref "LED_OUT3")
      (value "3mm Yellow Diffused")
      (footprint "eagle-import:LED_SILK")
      (libsource (lib "eagle-import") (part "LED_SILK"))
    )
    (comp (ref "LED_OUT4")
      (value "3mm Red Diffused")
      (footprint "eagle-import:LED_SILK")
      (libsource (lib "eagle-import") (part "LED_SILK"))
    )
    (comp (ref "LED_T1")
      (value "3mm Yellow Diffused")
      (footprint "eagle-import:LED_SILK")
      (libsource (lib "eagle-import") (part "LED_SILK"))
    )
    (comp (ref "LED_T2")
      (value "3mm Yellow Diffused")
      (footprint "eagle-import:LED_SILK")
      (libsource (lib "eagle-import") (part "LED_SILK"))
    )
    (comp (ref "LED_T4")
      (value "3mm Yellow Diffused")
      (footprint "eagle-import:LED_SILK")
      (libsource (lib "eagle-import") (part "LED_SILK"))
    )
    (comp (ref "LED_T8")
      (value "3mm Yellow Diffused")
      (footprint "eagle-import:LED_SILK")
      (libsource (lib "eagle-import") (part "LED_SILK"))
    )
    (comp (ref "S_BANK")
      (value "Mini Button")
      (footprint "eagle-import:TACTILE-PTH_SILK")
      (libsource (lib "eagle-import") (part "TAC_SWITCHTACTILE_PTH_SILK"))
    )
    (comp (ref "S_HOLD")
      (value "LED Button White")
      (footprint "eagle-import:LED_BUTTON_SILK")
      (libsource (lib "eagle-import") (part "LED_BUTTONLED_BUTTON_SILK"))
    )
    (comp (ref "S_MUTE_INS")
      (value "Mini Button")
      (footprint "eagle-import:TACTILE-PTH_SILK")
      (libsource (lib "eagle-import") (part "TAC_SWITCHTACTILE_PTH_SILK"))
    )
    (comp (ref "S_MUTE_OUTS")
      (value "Mini Button")
      (footprint "eagle-import:TACTILE-PTH_SILK")
      (libsource (lib "eagle-import") (part "TAC_SWITCHTACTILE_PTH_SILK"))
    )
    (comp (ref "S_TIME")
      (value "Mini Button")
      (footprint "eagle-import:TACTILE-PTH_SILK")
      (libsource (lib "eagle-import") (part "TAC_SWITCHTACTILE_PTH_SILK"))
    )
    (comp (ref "S_TRIG")
      (value "Mini Button")
      (footprint "eagle-import:TACTILE-PTH_SILK")
      (libsource (lib "eagle-import") (part "TAC_SWITCHTACTILE_PTH_SILK"))
    )
    (comp (ref "VR_DENS")
      (value "P-10K-B")
      (footprint "eagle-import:9MM_SNAP-IN_POT_SILK")
      (libsource (lib "eagle-import") (part "POT_9MM_SNAP-IN__"))
    )
    (comp (ref "VR_FDBK")
      (value "P-10K-B")
      (footprint "eagle-import:9MM_SNAP-IN_POT_SILK")
      (libsource (lib "eagle-import") (part "POT_9MM_SNAP-IN__"))
    )
    (comp (ref "VR_IN")
      (value "P-10K-B")
      (footprint "eagle-import:9MM_SNAP-IN_POT_SILK")
      (libsource (lib "eagle-import") (part "POT_9MM_SNAP-IN__"))
    )
    (comp (ref "VR_MIX")
      (value "P-10K-B")
      (footprint "eagle-import:9MM_SNAP-IN_POT_SILK")
      (libsource (lib "eagle-import") (part "POT_9MM_SNAP-IN__"))
    )
    (comp (ref "VR_OUT")
      (value "P-10K-B")
      (footprint "eagle-import:9MM_SNAP-IN_POT_SILK")
      (libsource (lib "eagle-import") (part "POT_9MM_SNAP-IN__"))
    )
    (comp (ref "VR_PAN")
      (value "P-10K-B")
      (footprint "eagle-import:9MM_SNAP-IN_POT_SILK")
      (libsource (lib "eagle-import") (part "POT_9MM_SNAP-IN__"))
    )
    (comp (ref "VR_PITCH")
      (value "P-10K-B")
      (footprint "eagle-import:9MM_SNAP-IN_POT_SILK")
      (libsource (lib "eagle-import") (part "POT_9MM_SNAP-IN__"))
    )
    (comp (ref "VR_POSI")
      (value "P-10K-B")
      (footprint "eagle-import:9MM_SNAP-IN_POT_SILK")
      (libsource (lib "eagle-import") (part "POT_9MM_SNAP-IN__"))
    )
    (comp (ref "VR_SIZE")
      (value "P-10K-B")
      (footprint "eagle-import:9MM_SNAP-IN_POT_SILK")
      (libsource (lib "eagle-import") (part "POT_9MM_SNAP-IN__"))
    )
    (comp (ref "VR_TEXT")
      (value "P-10K-B")
      (footprint "eagle-import:9MM_SNAP-IN_POT_SILK")
      (libsource (lib "eagle-import") (part "POT_9MM_SNAP-IN__"))
    )
    (comp (ref "VR_VERB")
      (value "P-10K-B")
      (footprint "eagle-import:9MM_SNAP-IN_POT_SILK")
      (libsource (lib "eagle-import") (part "POT_9MM_SNAP-IN__"))
    )
    (comp (ref "C1")
      (value "100NF")
      (footprint "eagle-import:C0603")
      (libsource (lib "eagle-import") (part "C-EUC0603"))
    )
    (comp (ref "C2")
      (value "100NF")
      (footprint "eagle-import:C0603")
      (libsource (lib "eagle-import") (part "C-EUC0603"))
    )
    (comp (ref "C3")
      (value "100NF")
      (footprint "eagle-import:C0603")
      (libsource (lib "eagle-import") (part "C-EUC0603"))
    )
    (comp (ref "C4")
      (value "10UF")
      (footprint "eagle-import:C0805")
      (libsource (lib "eagle-import") (part "C-EUC0805"))
    )
    (comp (ref "C6")
      (value "10UF")
      (footprint "eagle-import:C0805")
      (libsource (lib "eagle-import") (part "C-EUC0805"))
    )
    (comp (ref "C7")
      (value "10UF")
      (footprint "eagle-import:C0805")
      (libsource (lib "eagle-import") (part "C-EUC0805"))
    )
    (comp (ref "C9")
      (value "100NF")
      (footprint "eagle-import:C0603")
      (libsource (lib "eagle-import") (part "C-EUC0603"))
    )
    (comp (ref "C10")
      (value "10UF")
      (footprint "eagle-import:C0805")
      (libsource (lib "eagle-import") (part "C-EUC0805"))
    )
    (comp (ref "C22")
      (value "100NF")
      (footprint "eagle-import:C0603")
      (libsource (lib "eagle-import") (part "C-EUC0603"))
    )
    (comp (ref "C70")
      (value "470NF")
      (footprint "eagle-import:C0603")
      (libsource (lib "eagle-import") (part "C-EUC0603"))
    )
    (comp (ref "C71")
      (value "470NF")
      (footprint "eagle-import:C0603")
      (libsource (lib "eagle-import") (part "C-EUC0603"))
    )
    (comp (ref "C72")
      (value "100NF")
      (footprint "eagle-import:C0603")
      (libsource (lib "eagle-import") (part "C-EUC0603"))
    )
    (comp (ref "D1")
      (value "S1B")
      (footprint "eagle-import:SMADIODE")
      (libsource (lib "eagle-import") (part "S1B"))
    )
    (comp (ref "D2")
      (value "S1B")
      (footprint "eagle-import:SMADIODE")
      (libsource (lib "eagle-import") (part "S1B"))
    )
    (comp (ref "FB1")
      (value "FB")
      (footprint "eagle-import:WUERTH-ELEKTRONIK_0603")
      (fields (field (name "MPN") "MI0603J601R-10"))
      (libsource (lib "eagle-import") (part "FERRITE_BEAD_0603"))
    )
    (comp (ref "FB2")
      (value "FB")
      (footprint "eagle-import:WUERTH-ELEKTRONIK_0603")
      (fields (field (name "MPN") "MI0603J601R-10"))
      (libsource (lib "eagle-import") (part "FERRITE_BEAD_0603"))
    )
    (comp (ref "P1")
      (value "2X5 Male PTH Header")
      (footprint "eagle-import:2X5_LOCK")
      (libsource (lib "eagle-import") (part "M05X2_LOCK"))
    )
    (comp (ref "P3")
      (value "1X10 Female PTH header")
      (footprint "eagle-import:1X10_NO_SILK")
      (libsource (lib "eagle-import") (part "M10_NO_SILK"))
    )
    (comp (ref "P4")
      (value "1X10 Female PTH header")
      (footprint "eagle-import:1X10_NO_SILK")
      (libsource (lib "eagle-import") (part "M10_NO_SILK"))
    )
    (comp (ref "P5")
      (value "1X10 Female PTH header")
      (footprint "eagle-import:1X10_NO_SILK")
      (libsource (lib "eagle-import") (part "M10_NO_SILK"))
    )
    (comp (ref "P6")
      (value "1X10 Female PTH header")
      (footprint "eagle-import:1X10_NO_SILK")
      (libsource (lib "eagle-import") (part "M10_NO_SILK"))
    )
    (comp (ref "P7")
      (value "1X10 Female PTH header")
      (footprint "eagle-import:1X10_NO_SILK")
      (libsource (lib "eagle-import") (part "M10_NO_SILK"))
    )
    (comp (ref "P8")
      (value "1X10 Female PTH header")
      (footprint "eagle-import:1X10_NO_SILK")
      (libsource (lib "eagle-import") (part "M10_NO_SILK"))
    )
    (comp (ref "P9")
      (value "1X10 Male PTH header")
      (footprint "eagle-import:1X10_NO_SILK")
      (libsource (lib "eagle-import") (part "M10_NO_SILK"))
    )
    (comp (ref "P10")
      (value "1X10 Male PTH header")
      (footprint "eagle-import:1X10_NO_SILK")
      (libsource (lib "eagle-import") (part "M10_NO_SILK"))
    )
    (comp (ref "P11")
      (value "1X10 Male PTH header")
      (footprint "eagle-import:1X10_NO_SILK")
      (libsource (lib "eagle-import") (part "M10_NO_SILK"))
    )
    (comp (ref "P12")
      (value "1X10 Male PTH header")
      (footprint "eagle-import:1X10_NO_SILK")
      (libsource (lib "eagle-import") (part "M10_NO_SILK"))
    )
    (comp (ref "P13")
      (value "1X10 Male PTH header")
      (footprint "eagle-import:1X10_NO_SILK")
      (libsource (lib "eagle-import") (part "M10_NO_SILK"))
    )
    (comp (ref "P14")
      (value "1X10 Male PTH header")
      (footprint "eagle-import:1X10_NO_SILK")
      (libsource (lib "eagle-import") (part "M10_NO_SILK"))
    )
    (comp (ref "R4")
      (value "510R")
      (footprint "eagle-import:R0603")
      (libsource (lib "eagle-import") (part "R-US_R0603"))
    )
    (comp (ref "R104")
      (value "22K")
      (footprint "eagle-import:R0603")
      (libsource (lib "eagle-import") (part "R-US_R0603"))
    )
    (comp (ref "R105")
      (value "510R")
      (footprint "eagle-import:R0603")
      (libsource (lib "eagle-import") (part "R-US_R0603"))
    )
    (comp (ref "U1")
      (value "LD1117-3V3")
      (footprint "eagle-import:SOT223")
      (fields (field (name "MPN") "LD1117S33CTR"))
      (libsource (lib "eagle-import") (part "LD1117-3V3"))
    )
    (comp (ref "U4")
      (value "LD1117-3V3")
      (footprint "eagle-import:SOT223")
      (fields (field (name "MPN") "LD1117S33CTR"))
      (libsource (lib "eagle-import") (part "LD1117-3V3"))
    )
    (comp (ref "U5")
      (value "LM4040-10V")
      (footprint "eagle-import:DBZ_R-PDSO-G3")
      (fields (field (name "MPN") "LM4041A12IDBZR"))
      (libsource (lib "eagle-import") (part "LM4041DBZA12"))
    )
    (comp (ref "U14")
      (value "LM4040-2V5")
      (footprint "eagle-import:DBZ_R-PDSO-G3")
      (fields (field (name "MPN") "LM4041A12IDBZR"))
      (libsource (lib "eagle-import") (part "LM4041DBZA12"))
    )
    (comp (ref "U15")
      (value "LM4040-10V")
      (footprint "eagle-import:DBZ_R-PDSO-G3")
      (fields (field (name "MPN") "LM4041A12IDBZR"))
      (libsource (lib "eagle-import") (part "LM4041DBZA12"))
    )
  )
  (nets
    (net (code "1") (name "+3V3_A") (class "Default")
      (node (ref "C10") (pin "1") (pinfunction "1_1") (pintype "passive"))
      (node (ref "C11") (pin "1") (pinfunction "1_1") (pintype "passive"))
      (node (ref "C12") (pin "P$1") (pinfunction "POS_P$1") (pintype "passive"))
      (node (ref "C56") (pin "1") (pinfunction "1_1") (pintype "passive"))
      (node (ref "C57") (pin "1") (pinfunction "1_1") (pintype "passive"))
      (node (ref "C64") (pin "2") (pinfunction "2_2") (pintype "passive"))
      (node (ref "C65") (pin "2") (pinfunction "2_2") (pintype "passive"))
      (node (ref "C66") (pin "2") (pinfunction "2_2") (pintype "passive"))
      (node (ref "C69") (pin "1") (pinfunction "1_1") (pintype "passive"))
      (node (ref "P10") (pin "9") (pinfunction "9_9") (pintype "passive"))
      (node (ref "U10") (pin "4") (pinfunction "V+_4") (pintype "power_in"))
      (node (ref "U11") (pin "4") (pinfunction "V+_4") (pintype "power_in"))
      (node (ref "U17") (pin "16") (pinfunction "VCC_16") (pintype "power_in"))
      (node (ref "U3") (pin "21") (pinfunction "VREF+_21") (pintype "power_in"))
      (node (ref "U3") (pin "22") (pinfunction "VDDA_22") (pintype "power_in"))
      (node (ref "U4") (pin "2") (pinfunction "OUT_2") (pintype "passive"))
      (node (ref "U4") (pin "TAB") (pinfunction "OUT1_TAB") (pintype "passive"))
      (node (ref "U6") (pin "14") (pinfunction "AVDD_14") (pintype "bidirectional"))
      (node (ref "U6") (pin "8") (pinfunction "HPVDD_8") (pintype "bidirectional"))
      (node (ref "U9") (pin "4") (pinfunction "V+_4") (pintype "power_in"))
    )
    (net (code "2") (name "+3V3_D") (class "Default")
      (node (ref "C13") (pin "1") (pinfunction "1_1") (pintype "passive"))
      (node (ref "C14") (pin "P$1") (pinfunction "POS_P$1") (pintype "passive"))
      (node (ref "C4") (pin "1") (pinfunction "1_1") (pintype "passive"))
      (node (ref "C50") (pin "1") (pinfunction "1_1") (pintype "passive"))
      (node (ref "C51") (pin "1") (pinfunction "1_1") (pintype "passive"))
      (node (ref "C52") (pin "1") (pinfunction "1_1") (pintype "passive"))
      (node (ref "C53") (pin "1") (pinfunction "1_1") (pintype "passive"))
      (node (ref "C54") (pin "1") (pinfunction "1_1") (pintype "passive"))
      (node (ref "C55") (pin "1") (pinfunction "1_1") (pintype "passive"))
      (node (ref "P10") (pin "8") (pinfunction "8_8") (pintype "passive"))
      (node (ref "P2") (pin "1") (pinfunction "1_1") (pintype "passive"))
      (node (ref "R1") (pin "2") (pinfunction "2_2") (pintype "passive"))
      (node (ref "R106") (pin "2") (pinfunction "2_2") (pintype "passive"))
      (node (ref "R2") (pin "2") (pinfunction "2_2") (pintype "passive"))
      (node (ref "R55") (pin "2") (pinfunction "2_2") (pintype "passive"))
      (node (ref "R57") (pin "2") (pinfunction "2_2") (pintype "passive"))
      (node (ref "SW4") (pin "B") (pinfunction "S_B") (pintype "passive"))
      (node (ref "SW4") (pin "B'") (pinfunction "S1_B'") (pintype "passive"))
      (node (ref "U1") (pin "2") (pinfunction "OUT_2") (pintype "passive"))
      (node (ref "U1") (pin "TAB") (pinfunction "OUT1_TAB") (pintype "passive"))
      (node (ref "U3") (pin "100") (pinfunction "VDD_100") (pintype "power_in"))
      (node (ref "U3") (pin "11") (pinfunction "VDD_2_11") (pintype "power_in"))
      (node (ref "U3") (pin "19") (pinfunction "VDD_3_19") (pintype "power_in"))
      (node (ref "U3") (pin "28") (pinfunction "VDD_4_28") (pintype "power_in"))
      (node (ref "U3") (pin "50") (pinfunction "VDD_5_50") (pintype "power_in"))
      (node (ref "U3") (pin "75") (pinfunction "VDD_6_75") (pintype "power_in"))
      (node (ref "U6") (pin "1") (pinfunction "DBVDD_1") (pintype "bidirectional"))
      (node (ref "U6") (pin "27") (pinfunction "DCVDD_27") (pintype "bidirectional"))
    )
    (net (code "3") (name "+10V") (class "Default")
      (node (ref "C72") (pin "1") (pinfunction "1_1") (pintype "passive"))
      (node (ref "P10") (pin "10") (pinfunction "10_10") (pintype "passive"))
      (node (ref "R105") (pin "2") (pinfunction "2_2") (pintype "passive"))
      (node (ref "U15") (pin "1") (pinfunction "C_1") (pintype "passive"))
    )
    (net (code "4") (name "+12V") (class "Default")
      (node (ref "C1") (pin "1") (pinfunction "1_1") (pintype "passive"))
      (node (ref "C2") (pin "1") (pinfunction "1_1") (pintype "passive"))
      (node (ref "C58") (pin "2") (pinfunction "2_2") (pintype "passive"))
      (node (ref "C6") (pin "1") (pinfunction "1_1") (pintype "passive"))
      (node (ref "C67") (pin "2") (pinfunction "2_2") (pintype "passive"))
      (node (ref "C75") (pin "2") (pinfunction "2_2") (pintype "passive"))
      (node (ref "C76") (pin "2") (pinfunction "2_2") (pintype "passive"))
      (node (ref "C81") (pin "2") (pinfunction "2_2") (pintype "passive"))
      (node (ref "C9") (pin "1") (pinfunction "1_1") (pintype "passive"))
      (node (ref "D1") (pin "C") (pinfunction "C_C") (pintype "passive"))
      (node (ref "R105") (pin "1") (pinfunction "1_1") (pintype "passive"))
      (node (ref "U1") (pin "3") (pinfunction "IN_3") (pintype "input"))
      (node (ref "U12") (pin "4") (pinfunction "V+_4") (pintype "power_in"))
      (node (ref "U13") (pin "16") (pinfunction "V+_16") (pintype "power_in"))
      (node (ref "U18") (pin "16") (pinfunction "V+_16") (pintype "power_in"))
      (node (ref "U2") (pin "4") (pinfunction "V+_4") (pintype "power_in"))
      (node (ref "U4") (pin "3") (pinfunction "IN_3") (pintype "input"))
      (node (ref "U8") (pin "8") (pinfunction "V+_8") (pintype "power_in"))
    )
    (net (code "5") (name "-10V") (class "Default")
      (node (ref "C22") (pin "1") (pinfunction "1_1") (pintype "passive"))
      (node (ref "R31") (pin "1") (pinfunction "1_1") (pintype "passive"))
      (node (ref "R33") (pin "1") (pinfunction "1_1") (pintype "passive"))
      (node (ref "R34") (pin "1") (pinfunction "1_1") (pintype "passive"))
      (node (ref "R36") (pin "1") (pinfunction "1_1") (pintype "passive"))
      (node (ref "R38") (pin "1") (pinfunction "1_1") (pintype "passive"))
      (node (ref "R4") (pin "2") (pinfunction "2_2") (pintype "passive"))
      (node (ref "R40") (pin "1") (pinfunction "1_1") (pintype "passive"))
      (node (ref "R42") (pin "1") (pinfunction "1_1") (pintype "passive"))
      (node (ref "R43") (pin "1") (pinfunction "1_1") (pintype "passive"))
      (node (ref "R45") (pin "1") (pinfunction "1_1") (pintype "passive"))
      (node (ref "R50") (pin "1") (pinfunction "1_1") (pintype "passive"))
      (node (ref "U5") (pin "2") (pinfunction "A_2") (pintype "passive"))
    )
    (net (code "6") (name "-12V") (class "Default")
      (node (ref "C3") (pin "2") (pinfunction "2_2") (pintype "passive"))
      (node (ref "C59") (pin "1") (pinfunction "1_1") (pintype "passive"))
      (node (ref "C68") (pin "1") (pinfunction "1_1") (pintype "passive"))
      (node (ref "C7") (pin "2") (pinfunction "2_2") (pintype "passive"))
      (node (ref "C77") (pin "1") (pinfunction "1_1") (pintype "passive"))
      (node (ref "C78") (pin "1") (pinfunction "1_1") (pintype "passive"))
      (node (ref "C82") (pin "1") (pinfunction "1_1") (pintype "passive"))
      (node (ref "D2") (pin "A") (pinfunction "A_A") (pintype "passive"))
      (node (ref "R104") (pin "1") (pinfunction "1_1") (pintype "passive"))
      (node (ref "R4") (pin "1") (pinfunction "1_1") (pintype "passive"))
      (node (ref "U12") (pin "11") (pinfunction "V-_11") (pintype "power_in"))
      (node (ref "U13") (pin "9") (pinfunction "V-_9") (pintype "power_in"))
      (node (ref "U18") (pin "9") (pinfunction "V-_9") (pintype "power_in"))
      (node (ref "U2") (pin "11") (pinfunction "V-_11") (pintype "power_in"))
      (node (ref "U8") (pin "4") (pinfunction "V-_4") (pintype "power_in"))
    )
    (net (code "7") (name "ADC_EN") (class "Default")
      (node (ref "U17") (pin "6") (pinfunction "INH_6") (pintype "input"))
      (node (ref "U3") (pin "1") (pinfunction "PE2_1") (pintype "bidirectional"))
    )
    (net (code "8") (name "ADC_POT") (class "Default")
      (node (ref "U17") (pin "3") (pinfunction "X_3") (pintype "bidirectional"))
      (node (ref "U3") (pin "36") (pinfunction "PB1_36") (pintype "bidirectional"))
    )
    (net (code "9") (name "ADC_S0") (class "Default")
      (node (ref "U17") (pin "11") (pinfunction "A_11") (pintype "input"))
      (node (ref "U3") (pin "2") (pinfunction "PE3_2") (pintype "bidirectional"))
    )
    (net (code "10") (name "ADC_S1") (class "Default")
      (node (ref "U17") (pin "10") (pinfunction "B_10") (pintype "input"))
      (node (ref "U3") (pin "3") (pinfunction "PE4_3") (pintype "bidirectional"))
    )
    (net (code "11") (name "ADC_S2") (class "Default")
      (node (ref "U17") (pin "9") (pinfunction "C_9") (pintype "input"))
      (node (ref "U3") (pin "4") (pinfunction "PE5_4") (pintype "bidirectional"))
    )
    (net (code "12") (name "AREF_-2.5") (class "Default")
      (node (ref "C70") (pin "1") (pinfunction "1_1") (pintype "passive"))
      (node (ref "C71") (pin "1") (pinfunction "1_1") (pintype "passive"))
      (node (ref "R104") (pin "2") (pinfunction "2_2") (pintype "passive"))
      (node (ref "R64") (pin "2") (pinfunction "2_2") (pintype "passive"))
      (node (ref "R66") (pin "2") (pinfunction "2_2") (pintype "passive"))
      (node (ref "R73") (pin "2") (pinfunction "2_2") (pintype "passive"))
      (node (ref "R74") (pin "2") (pinfunction "2_2") (pintype "passive"))
      (node (ref "U14") (pin "2") (pinfunction "A_2") (pintype "passive"))
    )
    (net (code "13") (name "AUX_INTERNAL_MOD") (class "Default")
      (node (ref "P11") (pin "6") (pinfunction "6_6") (pintype "passive"))
      (node (ref "R111") (pin "1") (pinfunction "1_1") (pintype "passive"))
      (node (ref "U8") (pin "1") (pinfunction "OUT_1") (pintype "output"))
    )
    (net (code "14") (name "AUX_INTERNAL_MOD_RAW") (class "Default")
      (node (ref "U3") (pin "29") (pinfunction "PA4_29") (pintype "bidirectional"))
      (node (ref "U8") (pin "3") (pinfunction "+IN_3") (pintype "input"))
    )
    (net (code "15") (name "AUX_NORMAL") (class "Default")
      (node (ref "P11") (pin "8") (pinfunction "8_8") (pintype "passive"))
      (node (ref "R53") (pin "1") (pinfunction "1_1") (pintype "passive"))
    )
    (net (code "16") (name "BOOT_FLASH") (class "Default")
      (node (ref "R107") (pin "2") (pinfunction "2_2") (pintype "passive"))
      (node (ref "SW4") (pin "A") (pinfunction "P_A") (pintype "passive"))
      (node (ref "SW4") (pin "A'") (pinfunction "P1_A'") (pintype "passive"))
      (node (ref "U3") (pin "94") (pinfunction "BOOT0_94") (pintype "input"))
    )
    (net (code "17") (name "B_LED_BANK_1") (class "Default")
      (node (ref "P13") (pin "6") (pinfunction "6_6") (pintype "passive"))
      (node (ref "R18") (pin "1") (pinfunction "1_1") (pintype "passive"))
    )
    (net (code "18") (name "B_LED_BANK_2") (class "Default")
      (node (ref "P13") (pin "5") (pinfunction "5_5") (pintype "passive"))
      (node (ref "R19") (pin "1") (pinfunction "1_1") (pintype "passive"))
    )
    (net (code "19") (name "B_LED_BANK_3") (class "Default")
      (node (ref "P13") (pin "4") (pinfunction "4_4") (pintype "passive"))
      (node (ref "R22") (pin "1") (pinfunction "1_1") (pintype "passive"))
    )
    (net (code "20") (name "B_LED_BANK_4") (class "Default")
      (node (ref "P13") (pin "3") (pinfunction "3_3") (pintype "passive"))
      (node (ref "R24") (pin "1") (pinfunction "1_1") (pintype "passive"))
    )
    (net (code "21") (name "B_LED_TIME_1") (class "Default")
      (node (ref "P13") (pin "10") (pinfunction "10_10") (pintype "passive"))
      (node (ref "R25") (pin "1") (pinfunction "1_1") (pintype "passive"))
    )
    (net (code "22") (name "B_LED_TIME_2") (class "Default")
      (node (ref "P13") (pin "9") (pinfunction "9_9") (pintype "passive"))
      (node (ref "R27") (pin "1") (pinfunction "1_1") (pintype "passive"))
    )
    (net (code "23") (name "B_LED_TIME_3") (class "Default")
      (node (ref "P13") (pin "8") (pinfunction "8_8") (pintype "passive"))
      (node (ref "R29") (pin "1") (pinfunction "1_1") (pintype "passive"))
    )
    (net (code "24") (name "B_LED_TIME_4") (class "Default")
      (node (ref "P13") (pin "7") (pinfunction "7_7") (pintype "passive"))
      (node (ref "R30") (pin "1") (pinfunction "1_1") (pintype "passive"))
    )
    (net (code "25") (name "B_VU_METER_IN_1") (class "Default")
      (node (ref "P14") (pin "3") (pinfunction "3_3") (pintype "passive"))
      (node (ref "R17") (pin "1") (pinfunction "1_1") (pintype "passive"))
    )
    (net (code "26") (name "B_VU_METER_IN_2") (class "Default")
      (node (ref "P14") (pin "4") (pinfunction "4_4") (pintype "passive"))
      (node (ref "R15") (pin "1") (pinfunction "1_1") (pintype "passive"))
    )
    (net (code "27") (name "B_VU_METER_IN_3") (class "Default")
      (node (ref "P14") (pin "5") (pinfunction "5_5") (pintype "passive"))
      (node (ref "R13") (pin "1") (pinfunction "1_1") (pintype "passive"))
    )
    (net (code "28") (name "B_VU_METER_IN_4") (class "Default")
      (node (ref "P14") (pin "6") (pinfunction "6_6") (pintype "passive"))
      (node (ref "R12") (pin "1") (pinfunction "1_1") (pintype "passive"))
    )
    (net (code "29") (name "B_VU_METER_OUT_1") (class "Default")
      (node (ref "P14") (pin "10") (pinfunction "10_10") (pintype "passive"))
      (node (ref "R10") (pin "1") (pinfunction "1_1") (pintype "passive"))
    )
    (net (code "30") (name "B_VU_METER_OUT_2") (class "Default")
      (node (ref "P14") (pin "9") (pinfunction "9_9") (pintype "passive"))
      (node (ref "R8") (pin "1") (pinfunction "1_1") (pintype "passive"))
    )
    (net (code "31") (name "B_VU_METER_OUT_3") (class "Default")
      (node (ref "P14") (pin "8") (pinfunction "8_8") (pintype "passive"))
      (node (ref "R7") (pin "1") (pinfunction "1_1") (pintype "passive"))
    )
    (net (code "32") (name "B_VU_METER_OUT_4") (class "Default")
      (node (ref "P14") (pin "7") (pinfunction "7_7") (pintype "passive"))
      (node (ref "R5") (pin "1") (pinfunction "1_1") (pintype "passive"))
    )
    (net (code "33") (name "CV_VCA_OUT_LEVEL") (class "Default")
      (node (ref "C37") (pin "2") (pinfunction "2_2") (pintype "passive"))
      (node (ref "U12") (pin "7") (pinfunction "OUT_7") (pintype "output"))
      (node (ref "U13") (pin "14") (pinfunction "CTRL_14") (pintype "input"))
      (node (ref "U13") (pin "3") (pinfunction "CTRL_3") (pintype "input"))
      (node (ref "U18") (pin "3") (pinfunction "CTRL_3") (pintype "input"))
      (node (ref "U3") (pin "33") (pinfunction "PC4_33") (pintype "bidirectional"))
    )
    (net (code "34") (name "DENSITY_CV") (class "Default")
      (node (ref "C17") (pin "2") (pinfunction "2_2") (pintype "passive"))
      (node (ref "R16") (pin "2") (pinfunction "2_2") (pintype "passive"))
      (node (ref "U3") (pin "26") (pinfunction "PA3_26") (pintype "bidirectional"))
      (node (ref "U9") (pin "14") (pinfunction "OUT_14") (pintype "output"))
    )
    (net (code "35") (name "DENSITY_POT") (class "Default")
      (node (ref "P12") (pin "4") (pinfunction "4_4") (pintype "passive"))
      (node (ref "U17") (pin "4") (pinfunction "X7_4") (pintype "bidirectional"))
    )
    (net (code "36") (name "FEEDBACK_CV") (class "Default")
      (node (ref "C20") (pin "2") (pinfunction "2_2") (pintype "passive"))
      (node (ref "R23") (pin "2") (pinfunction "2_2") (pintype "passive"))
      (node (ref "U10") (pin "7") (pinfunction "OUT_7") (pintype "output"))
      (node (ref "U3") (pin "31") (pinfunction "PA6_31") (pintype "bidirectional"))
    )
    (net (code "37") (name "FEEDBACK_POT") (class "Default")
      (node (ref "P12") (pin "9") (pinfunction "9_9") (pintype "passive"))
      (node (ref "U17") (pin "14") (pinfunction "X1_14") (pintype "bidirectional"))
    )
    (net (code "38") (name "GATE_HOLD") (class "Default")
      (node (ref "Q1") (pin "C") (pinfunction "C_C") (pintype "passive"))
      (node (ref "R55") (pin "1") (pinfunction "1_1") (pintype "passive"))
      (node (ref "U3") (pin "44") (pinfunction "PE13_44") (pintype "bidirectional"))
    )
    (net (code "39") (name "GATE_TRIG") (class "Default")
      (node (ref "Q2") (pin "C") (pinfunction "C_C") (pintype "passive"))
      (node (ref "R57") (pin "1") (pinfunction "1_1") (pintype "passive"))
      (node (ref "U3") (pin "45") (pinfunction "PE14_45") (pintype "bidirectional"))
    )
    (net (code "40") (name "GND") (class "Default")
      (node (ref "C1") (pin "2") (pinfunction "2_2") (pintype "passive"))
      (node (ref "C10") (pin "2") (pinfunction "2_2") (pintype "passive"))
      (node (ref "C11") (pin "2") (pinfunction "2_2") (pintype "passive"))
      (node (ref "C12") (pin "P$2") (pinfunction "NEG_P$2") (pintype "passive"))
      (node (ref "C13") (pin "2") (pinfunction "2_2") (pintype "passive"))
      (node (ref "C14") (pin "P$2") (pinfunction "NEG_P$2") (pintype "passive"))
      (node (ref "C18") (pin "1") (pinfunction "1_1") (pintype "passive"))
      (node (ref "C19") (pin "1") (pinfunction "1_1") (pintype "passive"))
      (node (ref "C2") (pin "2") (pinfunction "2_2") (pintype "passive"))
      (node (ref "C22") (pin "2") (pinfunction "2_2") (pintype "passive"))
      (node (ref "C27") (pin "2") (pinfunction "2_2") (pintype "passive"))
      (node (ref "C28") (pin "2") (pinfunction "2_2") (pintype "passive"))
      (node (ref "C29") (pin "2") (pinfunction "2_2") (pintype "passive"))
      (node (ref "C3") (pin "1") (pinfunction "1_1") (pintype "passive"))
      (node (ref "C33") (pin "1") (pinfunction "1_1") (pintype "passive"))
      (node (ref "C36") (pin "2") (pinfunction "2_2") (pintype "passive"))
      (node (ref "C4") (pin "2") (pinfunction "2_2") (pintype "passive"))
      (node (ref "C40") (pin "2") (pinfunction "2_2") (pintype "passive"))
      (node (ref "C41") (pin "2") (pinfunction "2_2") (pintype "passive"))
      (node (ref "C44") (pin "1") (pinfunction "1_1") (pintype "passive"))
      (node (ref "C46") (pin "1") (pinfunction "1_1") (pintype "passive"))
      (node (ref "C47") (pin "1") (pinfunction "1_1") (pintype "passive"))
      (node (ref "C48") (pin "1") (pinfunction "1_1") (pintype "passive"))
      (node (ref "C49") (pin "1") (pinfunction "1_1") (pintype "passive"))
      (node (ref "C5") (pin "2") (pinfunction "2_2") (pintype "passive"))
      (node (ref "C50") (pin "2") (pinfunction "2_2") (pintype "passive"))
      (node (ref "C51") (pin "2") (pinfunction "2_2") (pintype "passive"))
      (node (ref "C52") (pin "2") (pinfunction "2_2") (pintype "passive"))
      (node (ref "C53") (pin "2") (pinfunction "2_2") (pintype "passive"))
      (node (ref "C54") (pin "2") (pinfunction "2_2") (pintype "passive"))
      (node (ref "C55") (pin "2") (pinfunction "2_2") (pintype "passive"))
      (node (ref "C56") (pin "2") (pinfunction "2_2") (pintype "passive"))
      (node (ref "C57") (pin "2") (pinfunction "2_2") (pintype "passive"))
      (node (ref "C58") (pin "1") (pinfunction "1_1") (pintype "passive"))
      (node (ref "C59") (pin "2") (pinfunction "2_2") (pintype "passive"))
      (node (ref "C6") (pin "2") (pinfunction "2_2") (pintype "passive"))
      (node (ref "C64") (pin "1") (pinfunction "1_1") (pintype "passive"))
      (node (ref "C65") (pin "1") (pinfunction "1_1") (pintype "passive"))
      (node (ref "C66") (pin "1") (pinfunction "1_1") (pintype "passive"))
      (node (ref "C67") (pin "1") (pinfunction "1_1") (pintype "passive"))
      (node (ref "C68") (pin "2") (pinfunction "2_2") (pintype "passive"))
      (node (ref "C69") (pin "2") (pinfunction "2_2") (pintype "passive"))
      (node (ref "C7") (pin "1") (pinfunction "1_1") (pintype "passive"))
      (node (ref "C70") (pin "2") (pinfunction "2_2") (pintype "passive"))
      (node (ref "C71") (pin "2") (pinfunction "2_2") (pintype "passive"))
      (node (ref "C72") (pin "2") (pinfunction "2_2") (pintype "passive"))
      (node (ref "C73") (pin "2") (pinfunction "2_2") (pintype "passive"))
      (node (ref "C74") (pin "2") (pinfunction "2_2") (pintype "passive"))
      (node (ref "C75") (pin "1") (pinfunction "1_1") (pintype "passive"))
      (node (ref "C76") (pin "1") (pinfunction "1_1") (pintype "passive"))
      (node (ref "C77") (pin "2") (pinfunction "2_2") (pintype "passive"))
      (node (ref "C78") (pin "2") (pinfunction "2_2") (pintype "passive"))
      (node (ref "C8") (pin "P$2") (pinfunction "NEG_P$2") (pintype "passive"))
      (node (ref "C81") (pin "1") (pinfunction "1_1") (pintype "passive"))
      (node (ref "C82") (pin "2") (pinfunction "2_2") (pintype "passive"))
      (node (ref "C9") (pin "2") (pinfunction "2_2") (pintype "passive"))
      (node (ref "JP1") (pin "1") (pinfunction "1_1") (pintype "passive"))
      (node (ref "P1") (pin "3") (pinfunction "3_3") (pintype "passive"))
      (node (ref "P1") (pin "4") (pinfunction "4_4") (pintype "passive"))
      (node (ref "P1") (pin "5") (pinfunction "5_5") (pintype "passive"))
      (node (ref "P1") (pin "6") (pinfunction "6_6") (pintype "passive"))
      (node (ref "P1") (pin "7") (pinfunction "7_7") (pintype "passive"))
      (node (ref "P1") (pin "8") (pinfunction "8_8") (pintype "passive"))
      (node (ref "P10") (pin "7") (pinfunction "7_7") (pintype "passive"))
      (node (ref "P11") (pin "10") (pinfunction "10_10") (pintype "passive"))
      (node (ref "P2") (pin "3") (pinfunction "3_3") (pintype "passive"))
      (node (ref "P2") (pin "5") (pinfunction "5_5") (pintype "passive"))
      (node (ref "P2") (pin "9") (pinfunction "9_9") (pintype "passive"))
      (node (ref "Q1") (pin "E") (pinfunction "E_E") (pintype "passive"))
      (node (ref "Q2") (pin "E") (pinfunction "E_E") (pintype "passive"))
      (node (ref "R107") (pin "1") (pinfunction "1_1") (pintype "passive"))
      (node (ref "R112") (pin "2") (pinfunction "2_2") (pintype "passive"))
      (node (ref "R113") (pin "2") (pinfunction "2_2") (pintype "passive"))
      (node (ref "R115") (pin "2") (pinfunction "2_2") (pintype "passive"))
      (node (ref "R52") (pin "1") (pinfunction "1_1") (pintype "passive"))
      (node (ref "R71") (pin "2") (pinfunction "2_2") (pintype "passive"))
      (node (ref "R82") (pin "2") (pinfunction "2_2") (pintype "passive"))
      (node (ref "R86") (pin "2") (pinfunction "2_2") (pintype "passive"))
      (node (ref "R87") (pin "2") (pinfunction "2_2") (pintype "passive"))
      (node (ref "SW5") (pin "A") (pinfunction "P_A") (pintype "passive"))
      (node (ref "SW5") (pin "A'") (pinfunction "P1_A'") (pintype "passive"))
      (node (ref "U1") (pin "1") (pinfunction "GND_1") (pintype "input"))
      (node (ref "U10") (pin "10") (pinfunction "+IN_10") (pintype "input"))
      (node (ref "U10") (pin "11") (pinfunction "V-_11") (pintype "power_in"))
      (node (ref "U10") (pin "12") (pinfunction "+IN_12") (pintype "input"))
      (node (ref "U10") (pin "3") (pinfunction "+IN_3") (pintype "input"))
      (node (ref "U10") (pin "5") (pinfunction "+IN_5") (pintype "input"))
      (node (ref "U11") (pin "10") (pinfunction "+IN_10") (pintype "input"))
      (node (ref "U11") (pin "11") (pinfunction "V-_11") (pintype "power_in"))
      (node (ref "U11") (pin "12") (pinfunction "+IN_12") (pintype "input"))
      (node (ref "U11") (pin "3") (pinfunction "+IN_3") (pintype "input"))
      (node (ref "U11") (pin "5") (pinfunction "+IN_5") (pintype "input"))
      (node (ref "U12") (pin "10") (pinfunction "+IN_10") (pintype "input"))
      (node (ref "U12") (pin "12") (pinfunction "+IN_12") (pintype "input"))
      (node (ref "U12") (pin "3") (pinfunction "+IN_3") (pintype "input"))
      (node (ref "U12") (pin "5") (pinfunction "+IN_5") (pintype "input"))
      (node (ref "U13") (pin "8") (pinfunction "GND_8") (pintype "power_in"))
      (node (ref "U14") (pin "1") (pinfunction "C_1") (pintype "passive"))
      (node (ref "U15") (pin "2") (pinfunction "A_2") (pintype "passive"))
      (node (ref "U17") (pin "7") (pinfunction "VEE_7") (pintype "power_in"))
      (node (ref "U17") (pin "8") (pinfunction "GND_8") (pintype "power_in"))
      (node (ref "U18") (pin "8") (pinfunction "GND_8") (pintype "power_in"))
      (node (ref "U2") (pin "10") (pinfunction "+IN_10") (pintype "input"))
      (node (ref "U2") (pin "5") (pinfunction "+IN_5") (pintype "input"))
      (node (ref "U3") (pin "10") (pinfunction "VSS_2_10") (pintype "power_in"))
      (node (ref "U3") (pin "20") (pinfunction "VSSA_20") (pintype "power_in"))
      (node (ref "U3") (pin "27") (pinfunction "VSS_3_27") (pintype "power_in"))
      (node (ref "U3") (pin "74") (pinfunction "VSS_4_74") (pintype "power_in"))
      (node (ref "U3") (pin "99") (pinfunction "VSS_99") (pintype "power_in"))
      (node (ref "U4") (pin "1") (pinfunction "GND_1") (pintype "input"))
      (node (ref "U5") (pin "1") (pinfunction "C_1") (pintype "passive"))
      (node (ref "U6") (pin "11") (pinfunction "HPGND_11") (pintype "bidirectional"))
      (node (ref "U6") (pin "15") (pinfunction "AGND_15") (pintype "bidirectional"))
      (node (ref "U6") (pin "21") (pinfunction "MODE_21") (pintype "bidirectional"))
      (node (ref "U6") (pin "22") (pinfunction "CSB_22") (pintype "bidirectional"))
      (node (ref "U6") (pin "28") (pinfunction "DGND_28") (pintype "bidirectional"))
      (node (ref "U9") (pin "10") (pinfunction "+IN_10") (pintype "input"))
      (node (ref "U9") (pin "11") (pinfunction "V-_11") (pintype "power_in"))
      (node (ref "U9") (pin "12") (pinfunction "+IN_12") (pintype "input"))
      (node (ref "U9") (pin "3") (pinfunction "+IN_3") (pintype "input"))
      (node (ref "U9") (pin "5") (pinfunction "+IN_5") (pintype "input"))
    )
    (net (code "41") (name "I2C_SCL") (class "Default")
      (node (ref "R1") (pin "1") (pinfunction "1_1") (pintype "passive"))
      (node (ref "U3") (pin "47") (pinfunction "PB10_47") (pintype "bidirectional"))
      (node (ref "U6") (pin "24") (pinfunction "SCLK_24") (pintype "bidirectional"))
    )
    (net (code "42") (name "I2C_SDA") (class "Default")
      (node (ref "R2") (pin "1") (pinfunction "1_1") (pintype "passive"))
      (node (ref "U3") (pin "48") (pinfunction "PB11_48") (pintype "bidirectional"))
      (node (ref "U6") (pin "23") (pinfunction "SDIN_23") (pintype "bidirectional"))
    )
    (net (code "43") (name "I2S_LRCK") (class "Default")
      (node (ref "U3") (pin "51") (pinfunction "PB12_51") (pintype "bidirectional"))
      (node (ref "U6") (pin "5") (pinfunction "DACLRC_5") (pintype "bidirectional"))
      (node (ref "U6") (pin "7") (pinfunction "ADCLRC_7") (pintype "bidirectional"))
    )
    (net (code "44") (name "I2S_SCK") (class "Default")
      (node (ref "U3") (pin "52") (pinfunction "PB13_52") (pintype "bidirectional"))
      (node (ref "U6") (pin "3") (pinfunction "BCLK_3") (pintype "bidirectional"))
    )
    (net (code "45") (name "I2S_SIN") (class "Default")
      (node (ref "U3") (pin "53") (pinfunction "PB14_53") (pintype "bidirectional"))
      (node (ref "U6") (pin "6") (pinfunction "ADCDAT_6") (pintype "bidirectional"))
    )
    (net (code "46") (name "I2S_SOUT") (class "Default")
      (node (ref "U3") (pin "54") (pinfunction "PB15_54") (pintype "bidirectional"))
      (node (ref "U6") (pin "4") (pinfunction "DACDAT_4") (pintype "bidirectional"))
    )
    (net (code "47") (name "IN_LVL_POT") (class "Default")
      (node (ref "P10") (pin "5") (pinfunction "5_5") (pintype "passive"))
      (node (ref "R69") (pin "2") (pinfunction "2_2") (pintype "passive"))
    )
    (net (code "48") (name "JTCK") (class "Default")
      (node (ref "P2") (pin "4") (pinfunction "4_4") (pintype "passive"))
      (node (ref "U3") (pin "76") (pinfunction "PA14_76") (pintype "bidirectional"))
    )
    (net (code "49") (name "JTDI") (class "Default")
      (node (ref "P2") (pin "8") (pinfunction "8_8") (pintype "passive"))
      (node (ref "U3") (pin "77") (pinfunction "PA15_77") (pintype "bidirectional"))
    )
    (net (code "50") (name "JTDO") (class "Default")
      (node (ref "P2") (pin "6") (pinfunction "6_6") (pintype "passive"))
      (node (ref "U3") (pin "89") (pinfunction "PB3_89") (pintype "bidirectional"))
    )
    (net (code "51") (name "JTMS") (class "Default")
      (node (ref "P2") (pin "2") (pinfunction "2_2") (pintype "passive"))
      (node (ref "U3") (pin "72") (pinfunction "PA13_72") (pintype "bidirectional"))
    )
    (net (code "52") (name "J_AUX_NORMAL") (class "Default")
      (node (ref "P11") (pin "7") (pinfunction "7_7") (pintype "passive"))
      (node (ref "R52") (pin "2") (pinfunction "2_2") (pintype "passive"))
      (node (ref "U8") (pin "5") (pinfunction "+IN_5") (pintype "input"))
    )
    (net (code "53") (name "J_DENSITY_CV") (class "Default")
      (node (ref "P9") (pin "7") (pinfunction "7_7") (pintype "passive"))
      (node (ref "R14") (pin "1") (pinfunction "1_1") (pintype "passive"))
    )
    (net (code "54") (name "J_FEEDBACK_CV") (class "Default")
      (node (ref "P9") (pin "1") (pinfunction "1_1") (pintype "passive"))
      (node (ref "R21") (pin "1") (pinfunction "1_1") (pintype "passive"))
    )
    (net (code "55") (name "J_GATE_HOLD") (class "Default")
      (node (ref "P11") (pin "5") (pinfunction "5_5") (pintype "passive"))
      (node (ref "R54") (pin "1") (pinfunction "1_1") (pintype "passive"))
    )
    (net (code "56") (name "J_GATE_TRIG") (class "Default")
      (node (ref "P11") (pin "4") (pinfunction "4_4") (pintype "passive"))
      (node (ref "R56") (pin "1") (pinfunction "1_1") (pintype "passive"))
    )
    (net (code "57") (name "J_I-LVL") (class "Default")
      (node (ref "P10") (pin "6") (pinfunction "6_6") (pintype "passive"))
      (node (ref "R70") (pin "2") (pinfunction "2_2") (pintype "passive"))
    )
    (net (code "58") (name "J_LIN") (class "Default")
      (node (ref "P12") (pin "2") (pinfunction "2_2") (pintype "passive"))
      (node (ref "R61") (pin "2") (pinfunction "2_2") (pintype "passive"))
    )
    (net (code "59") (name "J_LOUT") (class "Default")
      (node (ref "P10") (pin "2") (pinfunction "2_2") (pintype "passive"))
      (node (ref "R78") (pin "1") (pinfunction "1_1") (pintype "passive"))
    )
    (net (code "60") (name "J_MIX_CV") (class "Default")
      (node (ref "P9") (pin "9") (pinfunction "9_9") (pintype "passive"))
      (node (ref "R32") (pin "1") (pinfunction "1_1") (pintype "passive"))
    )
    (net (code "61") (name "J_O-LVL") (class "Default")
      (node (ref "P10") (pin "4") (pinfunction "4_4") (pintype "passive"))
      (node (ref "R76") (pin "2") (pinfunction "2_2") (pintype "passive"))
    )
    (net (code "62") (name "J_PAN_CV") (class "Default")
      (node (ref "P9") (pin "10") (pinfunction "10_10") (pintype "passive"))
      (node (ref "R26") (pin "1") (pinfunction "1_1") (pintype "passive"))
    )
    (net (code "63") (name "J_PITCH_CV") (class "Default")
      (node (ref "P9") (pin "8") (pinfunction "8_8") (pintype "passive"))
      (node (ref "R9") (pin "1") (pinfunction "1_1") (pintype "passive"))
    )
    (net (code "64") (name "J_POSITION_CV") (class "Default")
      (node (ref "P9") (pin "4") (pinfunction "4_4") (pintype "passive"))
      (node (ref "R20") (pin "1") (pinfunction "1_1") (pintype "passive"))
    )
    (net (code "65") (name "J_RIN") (class "Default")
      (node (ref "P12") (pin "1") (pinfunction "1_1") (pintype "passive"))
      (node (ref "R60") (pin "2") (pinfunction "2_2") (pintype "passive"))
    )
    (net (code "66") (name "J_ROUT") (class "Default")
      (node (ref "P10") (pin "1") (pinfunction "1_1") (pintype "passive"))
      (node (ref "R83") (pin "1") (pinfunction "1_1") (pintype "passive"))
    )
    (net (code "67") (name "J_SIZE_CV") (class "Default")
      (node (ref "P9") (pin "3") (pinfunction "3_3") (pintype "passive"))
      (node (ref "R3") (pin "1") (pinfunction "1_1") (pintype "passive"))
    )
    (net (code "68") (name "J_TEXT_CV") (class "Default")
      (node (ref "P9") (pin "2") (pinfunction "2_2") (pintype "passive"))
      (node (ref "R44") (pin "1") (pinfunction "1_1") (pintype "passive"))
    )
    (net (code "69") (name "J_VERB_CV") (class "Default")
      (node (ref "P9") (pin "6") (pinfunction "6_6") (pintype "passive"))
      (node (ref "R39") (pin "1") (pinfunction "1_1") (pintype "passive"))
    )
    (net (code "70") (name "J_VOCT_CV") (class "Default")
      (node (ref "P9") (pin "5") (pinfunction "5_5") (pintype "passive"))
      (node (ref "R49") (pin "1") (pinfunction "1_1") (pintype "passive"))
    )
    (net (code "71") (name "LED_BANK_1") (class "Default")
      (node (ref "R18") (pin "2") (pinfunction "2_2") (pintype "passive"))
      (node (ref "U3") (pin "85") (pinfunction "PD4_85") (pintype "bidirectional"))
    )
    (net (code "72") (name "LED_BANK_2") (class "Default")
      (node (ref "R19") (pin "2") (pinfunction "2_2") (pintype "passive"))
      (node (ref "U3") (pin "86") (pinfunction "PD5_86") (pintype "bidirectional"))
    )
    (net (code "73") (name "LED_BANK_3") (class "Default")
      (node (ref "R22") (pin "2") (pinfunction "2_2") (pintype "passive"))
      (node (ref "U3") (pin "87") (pinfunction "PD6_87") (pintype "bidirectional"))
    )
    (net (code "74") (name "LED_BANK_4") (class "Default")
      (node (ref "R24") (pin "2") (pinfunction "2_2") (pintype "passive"))
      (node (ref "U3") (pin "88") (pinfunction "PD7_88") (pintype "bidirectional"))
    )
    (net (code "75") (name "LED_HOLD") (class "Default")
      (node (ref "P11") (pin "3") (pinfunction "3_3") (pintype "passive"))
      (node (ref "U3") (pin "57") (pinfunction "PD10_57") (pintype "bidirectional"))
    )
    (net (code "76") (name "LED_TIME_1") (class "Default")
      (node (ref "R25") (pin "2") (pinfunction "2_2") (pintype "passive"))
      (node (ref "U3") (pin "81") (pinfunction "PD0_81") (pintype "bidirectional"))
    )
    (net (code "77") (name "LED_TIME_2") (class "Default")
      (node (ref "R27") (pin "2") (pinfunction "2_2") (pintype "passive"))
      (node (ref "U3") (pin "82") (pinfunction "PD1_82") (pintype "bidirectional"))
    )
    (net (code "78") (name "LED_TIME_3") (class "Default")
      (node (ref "R29") (pin "2") (pinfunction "2_2") (pintype "passive"))
      (node (ref "U3") (pin "83") (pinfunction "PD2_83") (pintype "bidirectional"))
    )
    (net (code "79") (name "LED_TIME_4") (class "Default")
      (node (ref "R30") (pin "2") (pinfunction "2_2") (pintype "passive"))
      (node (ref "U3") (pin "84") (pinfunction "PD3_84") (pintype "bidirectional"))
    )
    (net (code "80") (name "LIN") (class "Default")
      (node (ref "C35") (pin "P$1") (pinfunction "POS_P$1") (pintype "passive"))
      (node (ref "U6") (pin "20") (pinfunction "LLINEIN_20") (pintype "bidirectional"))
    )
    (net (code "81") (name "LOUT") (class "Default")
      (node (ref "C42") (pin "P$1") (pinfunction "POS_P$1") (pintype "passive"))
      (node (ref "U6") (pin "12") (pinfunction "LOUT_12") (pintype "bidirectional"))
    )
    (net (code "82") (name "MIX_CV") (class "Default")
      (node (ref "C23") (pin "2") (pinfunction "2_2") (pintype "passive"))
      (node (ref "R35") (pin "2") (pinfunction "2_2") (pintype "passive"))
      (node (ref "U10") (pin "14") (pinfunction "OUT_14") (pintype "output"))
      (node (ref "U3") (pin "35") (pinfunction "PB0_35") (pintype "bidirectional"))
    )
    (net (code "83") (name "MIX_POT") (class "Default")
      (node (ref "P12") (pin "7") (pinfunction "7_7") (pintype "passive"))
      (node (ref "U17") (pin "12") (pinfunction "X3_12") (pintype "bidirectional"))
    )
    (net (code "84") (name "Net-(C8-POS)") (class "Default")
      (node (ref "C5") (pin "1") (pinfunction "1_1") (pintype "passive"))
      (node (ref "C8") (pin "P$1") (pinfunction "POS_P$1") (pintype "passive"))
      (node (ref "U6") (pin "16") (pinfunction "VMID_16") (pintype "bidirectional"))
    )
    (net (code "85") (name "Net-(C27-Pad1)") (class "Default")
      (node (ref "C27") (pin "1") (pinfunction "1_1") (pintype "passive"))
      (node (ref "R58") (pin "1") (pinfunction "1_1") (pintype "passive"))
    )
    (net (code "86") (name "Net-(C28-Pad1)") (class "Default")
      (node (ref "C28") (pin "1") (pinfunction "1_1") (pintype "passive"))
      (node (ref "R59") (pin "1") (pinfunction "1_1") (pintype "passive"))
    )
    (net (code "87") (name "Net-(C29-Pad1)") (class "Default")
      (node (ref "C29") (pin "1") (pinfunction "1_1") (pintype "passive"))
      (node (ref "R63") (pin "1") (pinfunction "1_1") (pintype "passive"))
    )
    (net (code "88") (name "Net-(C35-NEG)") (class "Default")
      (node (ref "C33") (pin "2") (pinfunction "2_2") (pintype "passive"))
      (node (ref "C35") (pin "P$2") (pinfunction "NEG_P$2") (pintype "passive"))
      (node (ref "R65") (pin "1") (pinfunction "1_1") (pintype "passive"))
      (node (ref "R71") (pin "1") (pinfunction "1_1") (pintype "passive"))
    )
    (net (code "89") (name "Net-(C36-Pad1)") (class "Default")
      (node (ref "C36") (pin "1") (pinfunction "1_1") (pintype "passive"))
      (node (ref "R72") (pin "1") (pinfunction "1_1") (pintype "passive"))
    )
    (net (code "90") (name "Net-(C40-Pad1)") (class "Default")
      (node (ref "C40") (pin "1") (pinfunction "1_1") (pintype "passive"))
      (node (ref "R85") (pin "1") (pinfunction "1_1") (pintype "passive"))
    )
    (net (code "91") (name "Net-(C41-Pad1)") (class "Default")
      (node (ref "C41") (pin "1") (pinfunction "1_1") (pintype "passive"))
      (node (ref "R81") (pin "1") (pinfunction "1_1") (pintype "passive"))
    )
    (net (code "92") (name "Net-(C42-NEG)") (class "Default")
      (node (ref "C42") (pin "P$2") (pinfunction "NEG_P$2") (pintype "passive"))
      (node (ref "R80") (pin "2") (pinfunction "2_2") (pintype "passive"))
      (node (ref "R82") (pin "1") (pinfunction "1_1") (pintype "passive"))
    )
    (net (code "93") (name "Net-(C43-NEG)") (class "Default")
      (node (ref "C43") (pin "P$2") (pinfunction "NEG_P$2") (pintype "passive"))
      (node (ref "R84") (pin "2") (pinfunction "2_2") (pintype "passive"))
      (node (ref "R86") (pin "1") (pinfunction "1_1") (pintype "passive"))
    )
    (net (code "94") (name "Net-(C45-NEG)") (class "Default")
      (node (ref "C44") (pin "2") (pinfunction "2_2") (pintype "passive"))
      (node (ref "C45") (pin "P$2") (pinfunction "NEG_P$2") (pintype "passive"))
      (node (ref "R68") (pin "1") (pinfunction "1_1") (pintype "passive"))
      (node (ref "R87") (pin "1") (pinfunction "1_1") (pintype "passive"))
    )
    (net (code "95") (name "Net-(C73-Pad1)") (class "Default")
      (node (ref "C73") (pin "1") (pinfunction "1_1") (pintype "passive"))
      (node (ref "R109") (pin "1") (pinfunction "1_1") (pintype "passive"))
    )
    (net (code "96") (name "Net-(C74-Pad1)") (class "Default")
      (node (ref "C74") (pin "1") (pinfunction "1_1") (pintype "passive"))
      (node (ref "R110") (pin "1") (pinfunction "1_1") (pintype "passive"))
    )
    (net (code "97") (name "Net-(D1-PadA)") (class "Default")
      (node (ref "D1") (pin "A") (pinfunction "A_A") (pintype "passive"))
      (node (ref "FB1") (pin "2") (pinfunction "2_2") (pintype "passive"))
    )
    (net (code "98") (name "Net-(D2-PadC)") (class "Default")
      (node (ref "D2") (pin "C") (pinfunction "C_C") (pintype "passive"))
      (node (ref "FB2") (pin "2") (pinfunction "2_2") (pintype "passive"))
    )
    (net (code "99") (name "Net-(FB1-Pad1)") (class "Default")
      (node (ref "FB1") (pin "1") (pinfunction "1_1") (pintype "passive"))
      (node (ref "P1") (pin "1") (pinfunction "1_1") (pintype "passive"))
      (node (ref "P1") (pin "2") (pinfunction "2_2") (pintype "passive"))
    )
    (net (code "100") (name "Net-(FB2-Pad1)") (class "Default")
      (node (ref "FB2") (pin "1") (pinfunction "1_1") (pintype "passive"))
      (node (ref "P1") (pin "10") (pinfunction "10_10") (pintype "passive"))
      (node (ref "P1") (pin "9") (pinfunction "9_9") (pintype "passive"))
    )
    (net (code "101") (name "Net-(Q1-PadB)") (class "Default")
      (node (ref "Q1") (pin "B") (pinfunction "B_B") (pintype "passive"))
      (node (ref "R54") (pin "2") (pinfunction "2_2") (pintype "passive"))
    )
    (net (code "102") (name "Net-(Q2-PadB)") (class "Default")
      (node (ref "Q2") (pin "B") (pinfunction "B_B") (pintype "passive"))
      (node (ref "R56") (pin "2") (pinfunction "2_2") (pintype "passive"))
    )
    (net (code "103") (name "Net-(U2A-+IN)") (class "Default")
      (node (ref "C39") (pin "2") (pinfunction "2_2") (pintype "passive"))
      (node (ref "R79") (pin "1") (pinfunction "1_1") (pintype "passive"))
      (node (ref "U2") (pin "3") (pinfunction "+IN_3") (pintype "input"))
      (node (ref "U2") (pin "7") (pinfunction "OUT_7") (pintype "output"))
    )
    (net (code "104") (name "Net-(U2A--IN)") (class "Default")
      (node (ref "R115") (pin "1") (pinfunction "1_1") (pintype "passive"))
      (node (ref "R116") (pin "1") (pinfunction "1_1") (pintype "passive"))
      (node (ref "U2") (pin "2") (pinfunction "-IN_2") (pintype "input"))
    )
    (net (code "105") (name "Net-(U2A-OUT)") (class "Default")
      (node (ref "R116") (pin "2") (pinfunction "2_2") (pintype "passive"))
      (node (ref "R83") (pin "2") (pinfunction "2_2") (pintype "passive"))
      (node (ref "U2") (pin "1") (pinfunction "OUT_1") (pintype "output"))
    )
    (net (code "106") (name "Net-(U2C-OUT)") (class "Default")
      (node (ref "C38") (pin "2") (pinfunction "2_2") (pintype "passive"))
      (node (ref "R77") (pin "1") (pinfunction "1_1") (pintype "passive"))
      (node (ref "U2") (pin "12") (pinfunction "+IN_12") (pintype "input"))
      (node (ref "U2") (pin "8") (pinfunction "OUT_8") (pintype "output"))
    )
    (net (code "107") (name "Net-(U2D--IN)") (class "Default")
      (node (ref "R113") (pin "1") (pinfunction "1_1") (pintype "passive"))
      (node (ref "R114") (pin "1") (pinfunction "1_1") (pintype "passive"))
      (node (ref "U2") (pin "13") (pinfunction "-IN_13") (pintype "input"))
    )
    (net (code "108") (name "Net-(U2D-OUT)") (class "Default")
      (node (ref "R114") (pin "2") (pinfunction "2_2") (pintype "passive"))
      (node (ref "R78") (pin "2") (pinfunction "2_2") (pintype "passive"))
      (node (ref "U2") (pin "14") (pinfunction "OUT_14") (pintype "output"))
    )
    (net (code "109") (name "Net-(U3-PH0{slash}OSC_IN)") (class "Default")
      (node (ref "C47") (pin "2") (pinfunction "2_2") (pintype "passive"))
      (node (ref "U3") (pin "12") (pinfunction "PH0/OSC_IN_12") (pintype "bidirectional"))
      (node (ref "Y1") (pin "2") (pinfunction "2_2") (pintype "passive"))
    )
    (net (code "110") (name "Net-(U3-PH1{slash}OSC_OUT)") (class "Default")
      (node (ref "C46") (pin "2") (pinfunction "2_2") (pintype "passive"))
      (node (ref "U3") (pin "13") (pinfunction "PH1/OSC_OUT_13") (pintype "bidirectional"))
      (node (ref "Y1") (pin "1") (pinfunction "1_1") (pintype "passive"))
    )
    (net (code "111") (name "Net-(U6-XTI{slash}MCLK)") (class "Default")
      (node (ref "C18") (pin "2") (pinfunction "2_2") (pintype "passive"))
      (node (ref "U6") (pin "25") (pinfunction "XTI/MCLK_25") (pintype "bidirectional"))
      (node (ref "Y2") (pin "2") (pinfunction "2_2") (pintype "passive"))
    )
    (net (code "112") (name "Net-(U6-XTO)") (class "Default")
      (node (ref "C19") (pin "2") (pinfunction "2_2") (pintype "passive"))
      (node (ref "U6") (pin "26") (pinfunction "XTO_26") (pintype "bidirectional"))
      (node (ref "Y2") (pin "1") (pinfunction "1_1") (pintype "passive"))
    )
    (net (code "113") (name "Net-(U8A--IN)") (class "Default")
      (node (ref "R111") (pin "2") (pinfunction "2_2") (pintype "passive"))
      (node (ref "R112") (pin "1") (pinfunction "1_1") (pintype "passive"))
      (node (ref "U8") (pin "2") (pinfunction "-IN_2") (pintype "input"))
    )
    (net (code "114") (name "Net-(U8B--IN)") (class "Default")
      (node (ref "R53") (pin "2") (pinfunction "2_2") (pintype "passive"))
      (node (ref "U8") (pin "6") (pinfunction "-IN_6") (pintype "input"))
      (node (ref "U8") (pin "7") (pinfunction "OUT_7") (pintype "output"))
    )
    (net (code "115") (name "Net-(U9A--IN)") (class "Default")
      (node (ref "C34") (pin "1") (pinfunction "1_1") (pintype "passive"))
      (node (ref "R20") (pin "2") (pinfunction "2_2") (pintype "passive"))
      (node (ref "R37") (pin "1") (pinfunction "1_1") (pintype "passive"))
      (node (ref "R45") (pin "2") (pinfunction "2_2") (pintype "passive"))
      (node (ref "U9") (pin "2") (pinfunction "-IN_2") (pintype "input"))
    )
    (net (code "116") (name "Net-(U9B--IN)") (class "Default")
      (node (ref "C15") (pin "1") (pinfunction "1_1") (pintype "passive"))
      (node (ref "R3") (pin "2") (pinfunction "2_2") (pintype "passive"))
      (node (ref "R40") (pin "2") (pinfunction "2_2") (pintype "passive"))
      (node (ref "R6") (pin "1") (pinfunction "1_1") (pintype "passive"))
      (node (ref "U9") (pin "6") (pinfunction "-IN_6") (pintype "input"))
    )
    (net (code "117") (name "Net-(U9C--IN)") (class "Default")
      (node (ref "C16") (pin "1") (pinfunction "1_1") (pintype "passive"))
      (node (ref "R11") (pin "1") (pinfunction "1_1") (pintype "passive"))
      (node (ref "R38") (pin "2") (pinfunction "2_2") (pintype "passive"))
      (node (ref "R9") (pin "2") (pinfunction "2_2") (pintype "passive"))
      (node (ref "U9") (pin "9") (pinfunction "-IN_9") (pintype "input"))
    )
    (net (code "118") (name "Net-(U9D--IN)") (class "Default")
      (node (ref "C17") (pin "1") (pinfunction "1_1") (pintype "passive"))
      (node (ref "R14") (pin "2") (pinfunction "2_2") (pintype "passive"))
      (node (ref "R16") (pin "1") (pinfunction "1_1") (pintype "passive"))
      (node (ref "R36") (pin "2") (pinfunction "2_2") (pintype "passive"))
      (node (ref "U9") (pin "13") (pinfunction "-IN_13") (pintype "input"))
    )
    (net (code "119") (name "Net-(U10A--IN)") (class "Default")
      (node (ref "C25") (pin "1") (pinfunction "1_1") (pintype "passive"))
      (node (ref "R34") (pin "2") (pinfunction "2_2") (pintype "passive"))
      (node (ref "R44") (pin "2") (pinfunction "2_2") (pintype "passive"))
      (node (ref "R46") (pin "1") (pinfunction "1_1") (pintype "passive"))
      (node (ref "U10") (pin "2") (pinfunction "-IN_2") (pintype "input"))
    )
    (net (code "120") (name "Net-(U10B--IN)") (class "Default")
      (node (ref "C20") (pin "1") (pinfunction "1_1") (pintype "passive"))
      (node (ref "R21") (pin "2") (pinfunction "2_2") (pintype "passive"))
      (node (ref "R23") (pin "1") (pinfunction "1_1") (pintype "passive"))
      (node (ref "R43") (pin "2") (pinfunction "2_2") (pintype "passive"))
      (node (ref "U10") (pin "6") (pinfunction "-IN_6") (pintype "input"))
    )
    (net (code "121") (name "Net-(U10C--IN)") (class "Default")
      (node (ref "C21") (pin "1") (pinfunction "1_1") (pintype "passive"))
      (node (ref "R26") (pin "2") (pinfunction "2_2") (pintype "passive"))
      (node (ref "R28") (pin "1") (pinfunction "1_1") (pintype "passive"))
      (node (ref "R42") (pin "2") (pinfunction "2_2") (pintype "passive"))
      (node (ref "U10") (pin "9") (pinfunction "-IN_9") (pintype "input"))
    )
    (net (code "122") (name "Net-(U10D--IN)") (class "Default")
      (node (ref "C23") (pin "1") (pinfunction "1_1") (pintype "passive"))
      (node (ref "R31") (pin "2") (pinfunction "2_2") (pintype "passive"))
      (node (ref "R32") (pin "2") (pinfunction "2_2") (pintype "passive"))
      (node (ref "R35") (pin "1") (pinfunction "1_1") (pintype "passive"))
      (node (ref "U10") (pin "13") (pinfunction "-IN_13") (pintype "input"))
    )
    (net (code "123") (name "Net-(U11A--IN)") (class "Default")
      (node (ref "C24") (pin "1") (pinfunction "1_1") (pintype "passive"))
      (node (ref "R33") (pin "2") (pinfunction "2_2") (pintype "passive"))
      (node (ref "R39") (pin "2") (pinfunction "2_2") (pintype "passive"))
      (node (ref "R41") (pin "1") (pinfunction "1_1") (pintype "passive"))
      (node (ref "U11") (pin "2") (pinfunction "-IN_2") (pintype "input"))
    )
    (net (code "124") (name "Net-(U11B--IN)") (class "Default")
      (node (ref "C26") (pin "1") (pinfunction "1_1") (pintype "passive"))
      (node (ref "R49") (pin "2") (pinfunction "2_2") (pintype "passive"))
      (node (ref "R50") (pin "2") (pinfunction "2_2") (pintype "passive"))
      (node (ref "R51") (pin "1") (pinfunction "1_1") (pintype "passive"))
      (node (ref "U11") (pin "6") (pinfunction "-IN_6") (pintype "input"))
    )
    (net (code "125") (name "Net-(U11C--IN)") (class "Default")
      (node (ref "U11") (pin "8") (pinfunction "OUT_8") (pintype "output"))
      (node (ref "U11") (pin "9") (pinfunction "-IN_9") (pintype "input"))
    )
    (net (code "126") (name "Net-(U11D--IN)") (class "Default")
      (node (ref "U11") (pin "13") (pinfunction "-IN_13") (pintype "input"))
      (node (ref "U11") (pin "14") (pinfunction "OUT_14") (pintype "output"))
    )
    (net (code "127") (name "Net-(U12A--IN)") (class "Default")
      (node (ref "C32") (pin "1") (pinfunction "1_1") (pintype "passive"))
      (node (ref "R67") (pin "2") (pinfunction "2_2") (pintype "passive"))
      (node (ref "U12") (pin "2") (pinfunction "-IN_2") (pintype "input"))
      (node (ref "U18") (pin "5") (pinfunction "OUT_5") (pintype "output"))
    )
    (net (code "128") (name "Net-(U12A-OUT)") (class "Default")
      (node (ref "C32") (pin "2") (pinfunction "2_2") (pintype "passive"))
      (node (ref "R67") (pin "1") (pinfunction "1_1") (pintype "passive"))
      (node (ref "R68") (pin "2") (pinfunction "2_2") (pintype "passive"))
      (node (ref "U12") (pin "1") (pinfunction "OUT_1") (pintype "output"))
    )
    (net (code "129") (name "Net-(U12B--IN)") (class "Default")
      (node (ref "C37") (pin "1") (pinfunction "1_1") (pintype "passive"))
      (node (ref "R73") (pin "1") (pinfunction "1_1") (pintype "passive"))
      (node (ref "R75") (pin "1") (pinfunction "1_1") (pintype "passive"))
      (node (ref "R76") (pin "1") (pinfunction "1_1") (pintype "passive"))
      (node (ref "U12") (pin "6") (pinfunction "-IN_6") (pintype "input"))
      (node (ref "U18") (pin "4") (pinfunction "OUT_4") (pintype "output"))
    )
    (net (code "130") (name "Net-(U12C--IN)") (class "Default")
      (node (ref "C30") (pin "1") (pinfunction "1_1") (pintype "passive"))
      (node (ref "R64") (pin "1") (pinfunction "1_1") (pintype "passive"))
      (node (ref "R69") (pin "1") (pinfunction "1_1") (pintype "passive"))
      (node (ref "R70") (pin "1") (pinfunction "1_1") (pintype "passive"))
      (node (ref "U12") (pin "9") (pinfunction "-IN_9") (pintype "input"))
      (node (ref "U18") (pin "13") (pinfunction "OUT_13") (pintype "output"))
    )
    (net (code "131") (name "Net-(U12C-OUT)") (class "Default")
      (node (ref "C30") (pin "2") (pinfunction "2_2") (pintype "passive"))
      (node (ref "U12") (pin "8") (pinfunction "OUT_8") (pintype "output"))
      (node (ref "U18") (pin "11") (pinfunction "CTRL_11") (pintype "input"))
      (node (ref "U18") (pin "14") (pinfunction "CTRL_14") (pintype "input"))
      (node (ref "U18") (pin "6") (pinfunction "CTRL_6") (pintype "input"))
    )
    (net (code "132") (name "Net-(U12D--IN)") (class "Default")
      (node (ref "C31") (pin "1") (pinfunction "1_1") (pintype "passive"))
      (node (ref "R62") (pin "2") (pinfunction "2_2") (pintype "passive"))
      (node (ref "U12") (pin "13") (pinfunction "-IN_13") (pintype "input"))
      (node (ref "U18") (pin "12") (pinfunction "OUT_12") (pintype "output"))
    )
    (net (code "133") (name "Net-(U12D-OUT)") (class "Default")
      (node (ref "C31") (pin "2") (pinfunction "2_2") (pintype "passive"))
      (node (ref "R62") (pin "1") (pinfunction "1_1") (pintype "passive"))
      (node (ref "R65") (pin "2") (pinfunction "2_2") (pintype "passive"))
      (node (ref "U12") (pin "14") (pinfunction "OUT_14") (pintype "output"))
    )
    (net (code "134") (name "Net-(U13A-IN)") (class "Default")
      (node (ref "R84") (pin "1") (pinfunction "1_1") (pintype "passive"))
      (node (ref "R85") (pin "2") (pinfunction "2_2") (pintype "passive"))
      (node (ref "U13") (pin "2") (pinfunction "IN_2") (pintype "input"))
    )
    (net (code "135") (name "Net-(U13A-OUT)") (class "Default")
      (node (ref "C39") (pin "1") (pinfunction "1_1") (pintype "passive"))
      (node (ref "R79") (pin "2") (pinfunction "2_2") (pintype "passive"))
      (node (ref "U13") (pin "4") (pinfunction "OUT_4") (pintype "output"))
      (node (ref "U2") (pin "6") (pinfunction "-IN_6") (pintype "input"))
    )
    (net (code "136") (name "Net-(U13B-IN)") (class "Default")
      (node (ref "R109") (pin "2") (pinfunction "2_2") (pintype "passive"))
      (node (ref "U13") (pin "7") (pinfunction "IN_7") (pintype "input"))
    )
    (net (code "137") (name "Net-(U13C-IN)") (class "Default")
      (node (ref "R110") (pin "2") (pinfunction "2_2") (pintype "passive"))
      (node (ref "U13") (pin "10") (pinfunction "IN_10") (pintype "input"))
    )
    (net (code "138") (name "Net-(U13D-IN)") (class "Default")
      (node (ref "R80") (pin "1") (pinfunction "1_1") (pintype "passive"))
      (node (ref "R81") (pin "2") (pinfunction "2_2") (pintype "passive"))
      (node (ref "U13") (pin "15") (pinfunction "IN_15") (pintype "input"))
    )
    (net (code "139") (name "Net-(U13D-OUT)") (class "Default")
      (node (ref "C38") (pin "1") (pinfunction "1_1") (pintype "passive"))
      (node (ref "R77") (pin "2") (pinfunction "2_2") (pintype "passive"))
      (node (ref "U13") (pin "13") (pinfunction "OUT_13") (pintype "output"))
      (node (ref "U2") (pin "9") (pinfunction "-IN_9") (pintype "input"))
    )
    (net (code "140") (name "Net-(U18A-IN)") (class "Default")
      (node (ref "R72") (pin "2") (pinfunction "2_2") (pintype "passive"))
      (node (ref "R74") (pin "1") (pinfunction "1_1") (pintype "passive"))
      (node (ref "U18") (pin "2") (pinfunction "IN_2") (pintype "input"))
    )
    (net (code "141") (name "Net-(U18B-IN)") (class "Default")
      (node (ref "R58") (pin "2") (pinfunction "2_2") (pintype "passive"))
      (node (ref "R60") (pin "1") (pinfunction "1_1") (pintype "passive"))
      (node (ref "U18") (pin "7") (pinfunction "IN_7") (pintype "input"))
    )
    (net (code "142") (name "Net-(U18C-IN)") (class "Default")
      (node (ref "R59") (pin "2") (pinfunction "2_2") (pintype "passive"))
      (node (ref "R61") (pin "1") (pinfunction "1_1") (pintype "passive"))
      (node (ref "U18") (pin "10") (pinfunction "IN_10") (pintype "input"))
    )
    (net (code "143") (name "Net-(U18D-IN)") (class "Default")
      (node (ref "R63") (pin "2") (pinfunction "2_2") (pintype "passive"))
      (node (ref "R66") (pin "1") (pinfunction "1_1") (pintype "passive"))
      (node (ref "U18") (pin "15") (pinfunction "IN_15") (pintype "input"))
    )
    (net (code "144") (name "OUT_LVL_POT") (class "Default")
      (node (ref "P10") (pin "3") (pinfunction "3_3") (pintype "passive"))
      (node (ref "R75") (pin "2") (pinfunction "2_2") (pintype "passive"))
    )
    (net (code "145") (name "PAN_POT") (class "Default")
      (node (ref "P12") (pin "8") (pinfunction "8_8") (pintype "passive"))
      (node (ref "U17") (pin "13") (pinfunction "X0_13") (pintype "bidirectional"))
    )
    (net (code "146") (name "PITCH_CV") (class "Default")
      (node (ref "C16") (pin "2") (pinfunction "2_2") (pintype "passive"))
      (node (ref "R11") (pin "2") (pinfunction "2_2") (pintype "passive"))
      (node (ref "U3") (pin "25") (pinfunction "PA2_25") (pintype "bidirectional"))
      (node (ref "U9") (pin "8") (pinfunction "OUT_8") (pintype "output"))
    )
    (net (code "147") (name "PITCH_POT") (class "Default")
      (node (ref "P12") (pin "5") (pinfunction "5_5") (pintype "passive"))
      (node (ref "U17") (pin "2") (pinfunction "X6_2") (pintype "bidirectional"))
    )
    (net (code "148") (name "POSITION_CV") (class "Default")
      (node (ref "C34") (pin "2") (pinfunction "2_2") (pintype "passive"))
      (node (ref "R37") (pin "2") (pinfunction "2_2") (pintype "passive"))
      (node (ref "U3") (pin "23") (pinfunction "PA0/WKUP_23") (pintype "bidirectional"))
      (node (ref "U9") (pin "1") (pinfunction "OUT_1") (pintype "output"))
    )
    (net (code "149") (name "POSITION_POT") (class "Default")
      (node (ref "P12") (pin "6") (pinfunction "6_6") (pintype "passive"))
      (node (ref "U17") (pin "1") (pinfunction "X4_1") (pintype "bidirectional"))
    )
    (net (code "150") (name "RESET") (class "Default")
      (node (ref "P2") (pin "10") (pinfunction "10_10") (pintype "passive"))
      (node (ref "R106") (pin "1") (pinfunction "1_1") (pintype "passive"))
      (node (ref "SW5") (pin "B") (pinfunction "S_B") (pintype "passive"))
      (node (ref "SW5") (pin "B'") (pinfunction "S1_B'") (pintype "passive"))
      (node (ref "U3") (pin "14") (pinfunction "NRST_14") (pintype "bidirectional"))
    )
    (net (code "151") (name "RIN") (class "Default")
      (node (ref "C45") (pin "P$1") (pinfunction "POS_P$1") (pintype "passive"))
      (node (ref "U6") (pin "19") (pinfunction "RLINEIN_19") (pintype "bidirectional"))
    )
    (net (code "152") (name "ROUT") (class "Default")
      (node (ref "C43") (pin "P$1") (pinfunction "POS_P$1") (pintype "passive"))
      (node (ref "U6") (pin "13") (pinfunction "ROUT_13") (pintype "bidirectional"))
    )
    (net (code "153") (name "RX") (class "Default")
      (node (ref "JP1") (pin "4") (pinfunction "4_4") (pintype "passive"))
      (node (ref "U3") (pin "69") (pinfunction "PA10_69") (pintype "bidirectional"))
    )
    (net (code "154") (name "SHAPE_CV") (class "Default")
      (node (ref "C25") (pin "2") (pinfunction "2_2") (pintype "passive"))
      (node (ref "R46") (pin "2") (pinfunction "2_2") (pintype "passive"))
      (node (ref "U10") (pin "1") (pinfunction "OUT_1") (pintype "output"))
      (node (ref "U3") (pin "30") (pinfunction "PA5_30") (pintype "bidirectional"))
    )
    (net (code "155") (name "SIZE_CV") (class "Default")
      (node (ref "C15") (pin "2") (pinfunction "2_2") (pintype "passive"))
      (node (ref "R6") (pin "2") (pinfunction "2_2") (pintype "passive"))
      (node (ref "U3") (pin "24") (pinfunction "PA1_24") (pintype "bidirectional"))
      (node (ref "U9") (pin "7") (pinfunction "OUT_7") (pintype "output"))
    )
    (net (code "156") (name "SIZE_POT") (class "Default")
      (node (ref "P11") (pin "9") (pinfunction "9_9") (pintype "passive"))
      (node (ref "U3") (pin "16") (pinfunction "PC1_16") (pintype "bidirectional"))
    )
    (net (code "157") (name "SPACE_CV") (class "Default")
      (node (ref "C24") (pin "2") (pinfunction "2_2") (pintype "passive"))
      (node (ref "R41") (pin "2") (pinfunction "2_2") (pintype "passive"))
      (node (ref "U11") (pin "1") (pinfunction "OUT_1") (pintype "output"))
      (node (ref "U3") (pin "17") (pinfunction "PC2_17") (pintype "bidirectional"))
    )
    (net (code "158") (name "SW_BANK") (class "Default")
      (node (ref "P14") (pin "1") (pinfunction "1_1") (pintype "passive"))
      (node (ref "U3") (pin "43") (pinfunction "PE12_43") (pintype "bidirectional"))
    )
    (net (code "159") (name "SW_HOLD") (class "Default")
      (node (ref "P11") (pin "1") (pinfunction "1_1") (pintype "passive"))
      (node (ref "U3") (pin "41") (pinfunction "PE10_41") (pintype "bidirectional"))
    )
    (net (code "160") (name "SW_MUTE_INS") (class "Default")
      (node (ref "P13") (pin "1") (pinfunction "1_1") (pintype "passive"))
      (node (ref "U3") (pin "38") (pinfunction "PE7_38") (pintype "bidirectional"))
    )
    (net (code "161") (name "SW_MUTE_OUTS") (class "Default")
      (node (ref "P13") (pin "2") (pinfunction "2_2") (pintype "passive"))
      (node (ref "U3") (pin "39") (pinfunction "PE8_39") (pintype "bidirectional"))
    )
    (net (code "162") (name "SW_TIME") (class "Default")
      (node (ref "P14") (pin "2") (pinfunction "2_2") (pintype "passive"))
      (node (ref "U3") (pin "42") (pinfunction "PE11_42") (pintype "bidirectional"))
    )
    (net (code "163") (name "SW_TRIG") (class "Default")
      (node (ref "P11") (pin "2") (pinfunction "2_2") (pintype "passive"))
      (node (ref "U3") (pin "40") (pinfunction "PE9_40") (pintype "bidirectional"))
    )
    (net (code "164") (name "TEXT_POT") (class "Default")
      (node (ref "P12") (pin "3") (pinfunction "3_3") (pintype "passive"))
      (node (ref "U17") (pin "5") (pinfunction "X5_5") (pintype "bidirectional"))
    )
    (net (code "165") (name "TX") (class "Default")
      (node (ref "JP1") (pin "5") (pinfunction "5_5") (pintype "passive"))
      (node (ref "U3") (pin "68") (pinfunction "PA9_68") (pintype "bidirectional"))
    )
    (net (code "166") (name "T_+3V3_A") (class "Default")
      (node (ref "P5") (pin "9") (pinfunction "9_9") (pintype "passive"))
      (node (ref "VR_DENS") (pin "3") (pinfunction "3_3") (pintype "passive"))
      (node (ref "VR_FDBK") (pin "3") (pinfunction "3_3") (pintype "passive"))
      (node (ref "VR_MIX") (pin "3") (pinfunction "3_3") (pintype "passive"))
      (node (ref "VR_PAN") (pin "3") (pinfunction "3_3") (pintype "passive"))
      (node (ref "VR_PITCH") (pin "3") (pinfunction "3_3") (pintype "passive"))
      (node (ref "VR_POSI") (pin "3") (pinfunction "3_3") (pintype "passive"))
      (node (ref "VR_SIZE") (pin "3") (pinfunction "3_3") (pintype "passive"))
      (node (ref "VR_TEXT") (pin "3") (pinfunction "3_3") (pintype "passive"))
      (node (ref "VR_VERB") (pin "3") (pinfunction "3_3") (pintype "passive"))
    )
    (net (code "167") (name "T_+3V3_D") (class "Default")
      (node (ref "P5") (pin "8") (pinfunction "8_8") (pintype "passive"))
      (node (ref "S_BANK") (pin "3") (pinfunction "3_3") (pintype "passive"))
      (node (ref "S_HOLD") (pin "3") (pinfunction "3_3") (pintype "bidirectional"))
      (node (ref "S_MUTE_INS") (pin "3") (pinfunction "3_3") (pintype "passive"))
      (node (ref "S_MUTE_OUTS") (pin "3") (pinfunction "3_3") (pintype "passive"))
      (node (ref "S_TIME") (pin "3") (pinfunction "3_3") (pintype "passive"))
      (node (ref "S_TRIG") (pin "3") (pinfunction "3_3") (pintype "passive"))
    )
    (net (code "168") (name "T_+10V") (class "Default")
      (node (ref "P5") (pin "10") (pinfunction "10_10") (pintype "passive"))
      (node (ref "VR_IN") (pin "3") (pinfunction "3_3") (pintype "passive"))
      (node (ref "VR_OUT") (pin "3") (pinfunction "3_3") (pintype "passive"))
    )
    (net (code "169") (name "T_AUX_INTERNAL_MOD") (class "Default")
      (node (ref "J_AUX") (pin "NORM") (pinfunction "NORM_NORM") (pintype "passive"))
      (node (ref "P4") (pin "6") (pinfunction "6_6") (pintype "passive"))
    )
    (net (code "170") (name "T_AUX_NORMAL") (class "Default")
      (node (ref "J_DENS") (pin "NORM") (pinfunction "NORM_NORM") (pintype "passive"))
      (node (ref "J_FDBK") (pin "NORM") (pinfunction "NORM_NORM") (pintype "passive"))
      (node (ref "J_MIX") (pin "NORM") (pinfunction "NORM_NORM") (pintype "passive"))
      (node (ref "J_PAN") (pin "NORM") (pinfunction "NORM_NORM") (pintype "passive"))
      (node (ref "J_PITCH") (pin "NORM") (pinfunction "NORM_NORM") (pintype "passive"))
      (node (ref "J_POSI") (pin "NORM") (pinfunction "NORM_NORM") (pintype "passive"))
      (node (ref "J_SIZE") (pin "NORM") (pinfunction "NORM_NORM") (pintype "passive"))
      (node (ref "J_TEXT") (pin "NORM") (pinfunction "NORM_NORM") (pintype "passive"))
      (node (ref "J_VERB") (pin "NORM") (pinfunction "NORM_NORM") (pintype "passive"))
      (node (ref "P4") (pin "8") (pinfunction "8_8") (pintype "passive"))
    )
    (net (code "171") (name "T_DENSITY_POT") (class "Default")
      (node (ref "P6") (pin "4") (pinfunction "4_4") (pintype "passive"))
      (node (ref "VR_DENS") (pin "2") (pinfunction "2_2") (pintype "passive"))
    )
    (net (code "172") (name "T_FEEDBACK_POT") (class "Default")
      (node (ref "P6") (pin "9") (pinfunction "9_9") (pintype "passive"))
      (node (ref "VR_FDBK") (pin "2") (pinfunction "2_2") (pintype "passive"))
    )
    (net (code "173") (name "T_GND") (class "Default")
      (node (ref "J_AUX") (pin "GND") (pinfunction "GND_GND") (pintype "passive"))
      (node (ref "J_DENS") (pin "GND") (pinfunction "GND_GND") (pintype "passive"))
      (node (ref "J_FDBK") (pin "GND") (pinfunction "GND_GND") (pintype "passive"))
      (node (ref "J_HOLD") (pin "GND") (pinfunction "GND_GND") (pintype "passive"))
      (node (ref "J_HOLD") (pin "NORM") (pinfunction "NORM_NORM") (pintype "passive"))
      (node (ref "J_I-LVL") (pin "GND") (pinfunction "GND_GND") (pintype "passive"))
      (node (ref "J_LIN") (pin "GND") (pinfunction "GND_GND") (pintype "passive"))
      (node (ref "J_LOUT") (pin "GND") (pinfunction "GND_GND") (pintype "passive"))
      (node (ref "J_MIX") (pin "GND") (pinfunction "GND_GND") (pintype "passive"))
      (node (ref "J_O-LVL") (pin "GND") (pinfunction "GND_GND") (pintype "passive"))
      (node (ref "J_PAN") (pin "GND") (pinfunction "GND_GND") (pintype "passive"))
      (node (ref "J_PITCH") (pin "GND") (pinfunction "GND_GND") (pintype "passive"))
      (node (ref "J_POSI") (pin "GND") (pinfunction "GND_GND") (pintype "passive"))
      (node (ref "J_RIN") (pin "GND") (pinfunction "GND_GND") (pintype "passive"))
      (node (ref "J_ROUT") (pin "GND") (pinfunction "GND_GND") (pintype "passive"))
      (node (ref "J_SIZE") (pin "GND") (pinfunction "GND_GND") (pintype "passive"))
      (node (ref "J_TEXT") (pin "GND") (pinfunction "GND_GND") (pintype "passive"))
      (node (ref "J_TRIG") (pin "GND") (pinfunction "GND_GND") (pintype "passive"))
      (node (ref "J_TRIG") (pin "NORM") (pinfunction "NORM_NORM") (pintype "passive"))
      (node (ref "J_VERB") (pin "GND") (pinfunction "GND_GND") (pintype "passive"))
      (node (ref "J_VOCT") (pin "GND") (pinfunction "GND_GND") (pintype "passive"))
      (node (ref "LED_A") (pin "K") (pinfunction "C_K") (pintype "passive"))
      (node (ref "LED_B") (pin "K") (pinfunction "C_K") (pintype "passive"))
      (node (ref "LED_C") (pin "K") (pinfunction "C_K") (pintype "passive"))
      (node (ref "LED_D") (pin "K") (pinfunction "C_K") (pintype "passive"))
      (node (ref "LED_IN1") (pin "K") (pinfunction "C_K") (pintype "passive"))
      (node (ref "LED_IN2") (pin "K") (pinfunction "C_K") (pintype "passive"))
      (node (ref "LED_IN3") (pin "K") (pinfunction "C_K") (pintype "passive"))
      (node (ref "LED_IN4") (pin "K") (pinfunction "C_K") (pintype "passive"))
      (node (ref "LED_OUT1") (pin "K") (pinfunction "C_K") (pintype "passive"))
      (node (ref "LED_OUT2") (pin "K") (pinfunction "C_K") (pintype "passive"))
      (node (ref "LED_OUT3") (pin "K") (pinfunction "C_K") (pintype "passive"))
      (node (ref "LED_OUT4") (pin "K") (pinfunction "C_K") (pintype "passive"))
      (node (ref "LED_T1") (pin "K") (pinfunction "C_K") (pintype "passive"))
      (node (ref "LED_T2") (pin "K") (pinfunction "C_K") (pintype "passive"))
      (node (ref "LED_T4") (pin "K") (pinfunction "C_K") (pintype "passive"))
      (node (ref "LED_T8") (pin "K") (pinfunction "C_K") (pintype "passive"))
      (node (ref "P4") (pin "10") (pinfunction "10_10") (pintype "passive"))
      (node (ref "P5") (pin "7") (pinfunction "7_7") (pintype "passive"))
      (node (ref "S_HOLD") (pin "LED_K") (pinfunction "LED_K_LED_K") (pintype "bidirectional"))
      (node (ref "VR_DENS") (pin "1") (pinfunction "1_1") (pintype "passive"))
      (node (ref "VR_FDBK") (pin "1") (pinfunction "1_1") (pintype "passive"))
      (node (ref "VR_IN") (pin "1") (pinfunction "1_1") (pintype "passive"))
      (node (ref "VR_MIX") (pin "1") (pinfunction "1_1") (pintype "passive"))
      (node (ref "VR_OUT") (pin "1") (pinfunction "1_1") (pintype "passive"))
      (node (ref "VR_PAN") (pin "1") (pinfunction "1_1") (pintype "passive"))
      (node (ref "VR_PITCH") (pin "1") (pinfunction "1_1") (pintype "passive"))
      (node (ref "VR_POSI") (pin "1") (pinfunction "1_1") (pintype "passive"))
      (node (ref "VR_SIZE") (pin "1") (pinfunction "1_1") (pintype "passive"))
      (node (ref "VR_TEXT") (pin "1") (pinfunction "1_1") (pintype "passive"))
      (node (ref "VR_VERB") (pin "1") (pinfunction "1_1") (pintype "passive"))
    )
    (net (code "174") (name "T_IN_LVL_POT") (class "Default")
      (node (ref "P5") (pin "5") (pinfunction "5_5") (pintype "passive"))
      (node (ref "VR_IN") (pin "2") (pinfunction "2_2") (pintype "passive"))
    )
    (net (code "175") (name "T_J_AUX_NORMAL") (class "Default")
      (node (ref "J_AUX") (pin "TIP") (pinfunction "TIP_TIP") (pintype "passive"))
      (node (ref "P4") (pin "7") (pinfunction "7_7") (pintype "passive"))
    )
    (net (code "176") (name "T_J_DENSITY_CV") (class "Default")
      (node (ref "J_DENS") (pin "TIP") (pinfunction "TIP_TIP") (pintype "passive"))
      (node (ref "P3") (pin "7") (pinfunction "7_7") (pintype "passive"))
    )
    (net (code "177") (name "T_J_FEEDBACK_CV") (class "Default")
      (node (ref "J_FDBK") (pin "TIP") (pinfunction "TIP_TIP") (pintype "passive"))
      (node (ref "P3") (pin "1") (pinfunction "1_1") (pintype "passive"))
    )
    (net (code "178") (name "T_J_GATE_HOLD") (class "Default")
      (node (ref "J_HOLD") (pin "TIP") (pinfunction "TIP_TIP") (pintype "passive"))
      (node (ref "P4") (pin "5") (pinfunction "5_5") (pintype "passive"))
    )
    (net (code "179") (name "T_J_GATE_TRIG") (class "Default")
      (node (ref "J_TRIG") (pin "TIP") (pinfunction "TIP_TIP") (pintype "passive"))
      (node (ref "P4") (pin "4") (pinfunction "4_4") (pintype "passive"))
    )
    (net (code "180") (name "T_J_I-LVL") (class "Default")
      (node (ref "J_I-LVL") (pin "TIP") (pinfunction "TIP_TIP") (pintype "passive"))
      (node (ref "P5") (pin "6") (pinfunction "6_6") (pintype "passive"))
    )
    (net (code "181") (name "T_J_LIN") (class "Default")
      (node (ref "J_LIN") (pin "TIP") (pinfunction "TIP_TIP") (pintype "passive"))
      (node (ref "J_RIN") (pin "NORM") (pinfunction "NORM_NORM") (pintype "passive"))
      (node (ref "P6") (pin "2") (pinfunction "2_2") (pintype "passive"))
    )
    (net (code "182") (name "T_J_LOUT") (class "Default")
      (node (ref "J_LOUT") (pin "TIP") (pinfunction "TIP_TIP") (pintype "passive"))
      (node (ref "P5") (pin "2") (pinfunction "2_2") (pintype "passive"))
    )
    (net (code "183") (name "T_J_MIX_CV") (class "Default")
      (node (ref "J_MIX") (pin "TIP") (pinfunction "TIP_TIP") (pintype "passive"))
      (node (ref "P3") (pin "9") (pinfunction "9_9") (pintype "passive"))
    )
    (net (code "184") (name "T_J_O-LVL") (class "Default")
      (node (ref "J_O-LVL") (pin "TIP") (pinfunction "TIP_TIP") (pintype "passive"))
      (node (ref "P5") (pin "4") (pinfunction "4_4") (pintype "passive"))
    )
    (net (code "185") (name "T_J_PAN_CV") (class "Default")
      (node (ref "J_PAN") (pin "TIP") (pinfunction "TIP_TIP") (pintype "passive"))
      (node (ref "P3") (pin "10") (pinfunction "10_10") (pintype "passive"))
    )
    (net (code "186") (name "T_J_PITCH_CV") (class "Default")
      (node (ref "J_PITCH") (pin "TIP") (pinfunction "TIP_TIP") (pintype "passive"))
      (node (ref "P3") (pin "8") (pinfunction "8_8") (pintype "passive"))
    )
    (net (code "187") (name "T_J_POSITION_CV") (class "Default")
      (node (ref "J_POSI") (pin "TIP") (pinfunction "TIP_TIP") (pintype "passive"))
      (node (ref "P3") (pin "4") (pinfunction "4_4") (pintype "passive"))
    )
    (net (code "188") (name "T_J_RIN") (class "Default")
      (node (ref "J_RIN") (pin "TIP") (pinfunction "TIP_TIP") (pintype "passive"))
      (node (ref "P6") (pin "1") (pinfunction "1_1") (pintype "passive"))
    )
    (net (code "189") (name "T_J_ROUT") (class "Default")
      (node (ref "J_ROUT") (pin "TIP") (pinfunction "TIP_TIP") (pintype "passive"))
      (node (ref "P5") (pin "1") (pinfunction "1_1") (pintype "passive"))
    )
    (net (code "190") (name "T_J_SIZE_CV") (class "Default")
      (node (ref "J_SIZE") (pin "TIP") (pinfunction "TIP_TIP") (pintype "passive"))
      (node (ref "P3") (pin "3") (pinfunction "3_3") (pintype "passive"))
    )
    (net (code "191") (name "T_J_TEXT_CV") (class "Default")
      (node (ref "J_TEXT") (pin "TIP") (pinfunction "TIP_TIP") (pintype "passive"))
      (node (ref "P3") (pin "2") (pinfunction "2_2") (pintype "passive"))
    )
    (net (code "192") (name "T_J_VERB_CV") (class "Default")
      (node (ref "J_VERB") (pin "TIP") (pinfunction "TIP_TIP") (pintype "passive"))
      (node (ref "P3") (pin "6") (pinfunction "6_6") (pintype "passive"))
    )
    (net (code "193") (name "T_J_VOCT_CV") (class "Default")
      (node (ref "J_VOCT") (pin "TIP") (pinfunction "TIP_TIP") (pintype "passive"))
      (node (ref "P3") (pin "5") (pinfunction "5_5") (pintype "passive"))
    )
    (net (code "194") (name "T_LED_BANK_1") (class "Default")
      (node (ref "LED_A") (pin "A") (pinfunction "A_A") (pintype "passive"))
      (node (ref "P7") (pin "6") (pinfunction "6_6") (pintype "passive"))
    )
    (net (code "195") (name "T_LED_BANK_2") (class "Default")
      (node (ref "LED_B") (pin "A") (pinfunction "A_A") (pintype "passive"))
      (node (ref "P7") (pin "5") (pinfunction "5_5") (pintype "passive"))
    )
    (net (code "196") (name "T_LED_BANK_3") (class "Default")
      (node (ref "LED_C") (pin "A") (pinfunction "A_A") (pintype "passive"))
      (node (ref "P7") (pin "4") (pinfunction "4_4") (pintype "passive"))
    )
    (net (code "197") (name "T_LED_BANK_4") (class "Default")
      (node (ref "LED_D") (pin "A") (pinfunction "A_A") (pintype "passive"))
      (node (ref "P7") (pin "3") (pinfunction "3_3") (pintype "passive"))
    )
    (net (code "198") (name "T_LED_HOLD") (class "Default")
      (node (ref "P4") (pin "3") (pinfunction "3_3") (pintype "passive"))
      (node (ref "S_HOLD") (pin "LED_A") (pinfunction "LED_A_LED_A") (pintype "bidirectional"))
    )
    (net (code "199") (name "T_LED_TIME_1") (class "Default")
      (node (ref "LED_T1") (pin "A") (pinfunction "A_A") (pintype "passive"))
      (node (ref "P7") (pin "10") (pinfunction "10_10") (pintype "passive"))
    )
    (net (code "200") (name "T_LED_TIME_2") (class "Default")
      (node (ref "LED_T2") (pin "A") (pinfunction "A_A") (pintype "passive"))
      (node (ref "P7") (pin "9") (pinfunction "9_9") (pintype "passive"))
    )
    (net (code "201") (name "T_LED_TIME_3") (class "Default")
      (node (ref "LED_T4") (pin "A") (pinfunction "A_A") (pintype "passive"))
      (node (ref "P7") (pin "8") (pinfunction "8_8") (pintype "passive"))
    )
    (net (code "202") (name "T_LED_TIME_4") (class "Default")
      (node (ref "LED_T8") (pin "A") (pinfunction "A_A") (pintype "passive"))
      (node (ref "P7") (pin "7") (pinfunction "7_7") (pintype "passive"))
    )
    (net (code "203") (name "T_MIX_POT") (class "Default")
      (node (ref "P6") (pin "7") (pinfunction "7_7") (pintype "passive"))
      (node (ref "VR_MIX") (pin "2") (pinfunction "2_2") (pintype "passive"))
    )
    (net (code "204") (name "T_OUT_LVL_POT") (class "Default")
      (node (ref "P5") (pin "3") (pinfunction "3_3") (pintype "passive"))
      (node (ref "VR_OUT") (pin "2") (pinfunction "2_2") (pintype "passive"))
    )
    (net (code "205") (name "T_PAN_POT") (class "Default")
      (node (ref "P6") (pin "8") (pinfunction "8_8") (pintype "passive"))
      (node (ref "VR_PAN") (pin "2") (pinfunction "2_2") (pintype "passive"))
    )
    (net (code "206") (name "T_PITCH_POT") (class "Default")
      (node (ref "P6") (pin "5") (pinfunction "5_5") (pintype "passive"))
      (node (ref "VR_PITCH") (pin "2") (pinfunction "2_2") (pintype "passive"))
    )
    (net (code "207") (name "T_POSITION_POT") (class "Default")
      (node (ref "P6") (pin "6") (pinfunction "6_6") (pintype "passive"))
      (node (ref "VR_POSI") (pin "2") (pinfunction "2_2") (pintype "passive"))
    )
    (net (code "208") (name "T_SIZE_POT") (class "Default")
      (node (ref "P4") (pin "9") (pinfunction "9_9") (pintype "passive"))
      (node (ref "VR_SIZE") (pin "2") (pinfunction "2_2") (pintype "passive"))
    )
    (net (code "209") (name "T_SW_BANK") (class "Default")
      (node (ref "P8") (pin "1") (pinfunction "1_1") (pintype "passive"))
      (node (ref "S_BANK") (pin "1") (pinfunction "1_1") (pintype "passive"))
    )
    (net (code "210") (name "T_SW_HOLD") (class "Default")
      (node (ref "P4") (pin "1") (pinfunction "1_1") (pintype "passive"))
      (node (ref "S_HOLD") (pin "2") (pinfunction "2_2") (pintype "bidirectional"))
    )
    (net (code "211") (name "T_SW_MUTE_INS") (class "Default")
      (node (ref "P7") (pin "1") (pinfunction "1_1") (pintype "passive"))
      (node (ref "S_MUTE_INS") (pin "1") (pinfunction "1_1") (pintype "passive"))
    )
    (net (code "212") (name "T_SW_MUTE_OUTS") (class "Default")
      (node (ref "P7") (pin "2") (pinfunction "2_2") (pintype "passive"))
      (node (ref "S_MUTE_OUTS") (pin "1") (pinfunction "1_1") (pintype "passive"))
    )
    (net (code "213") (name "T_SW_TIME") (class "Default")
      (node (ref "P8") (pin "2") (pinfunction "2_2") (pintype "passive"))
      (node (ref "S_TIME") (pin "1") (pinfunction "1_1") (pintype "passive"))
    )
    (net (code "214") (name "T_SW_TRIG") (class "Default")
      (node (ref "P4") (pin "2") (pinfunction "2_2") (pintype "passive"))
      (node (ref "S_TRIG") (pin "1") (pinfunction "1_1") (pintype "passive"))
    )
    (net (code "215") (name "T_TEXT_POT") (class "Default")
      (node (ref "P6") (pin "3") (pinfunction "3_3") (pintype "passive"))
      (node (ref "VR_TEXT") (pin "2") (pinfunction "2_2") (pintype "passive"))
    )
    (net (code "216") (name "T_VERB_POT") (class "Default")
      (node (ref "P6") (pin "10") (pinfunction "10_10") (pintype "passive"))
      (node (ref "VR_VERB") (pin "2") (pinfunction "2_2") (pintype "passive"))
    )
    (net (code "217") (name "T_VU_METER_IN_1") (class "Default")
      (node (ref "LED_IN1") (pin "A") (pinfunction "A_A") (pintype "passive"))
      (node (ref "P8") (pin "3") (pinfunction "3_3") (pintype "passive"))
    )
    (net (code "218") (name "T_VU_METER_IN_2") (class "Default")
      (node (ref "LED_IN2") (pin "A") (pinfunction "A_A") (pintype "passive"))
      (node (ref "P8") (pin "4") (pinfunction "4_4") (pintype "passive"))
    )
    (net (code "219") (name "T_VU_METER_IN_3") (class "Default")
      (node (ref "LED_IN3") (pin "A") (pinfunction "A_A") (pintype "passive"))
      (node (ref "P8") (pin "5") (pinfunction "5_5") (pintype "passive"))
    )
    (net (code "220") (name "T_VU_METER_IN_4") (class "Default")
      (node (ref "LED_IN4") (pin "A") (pinfunction "A_A") (pintype "passive"))
      (node (ref "P8") (pin "6") (pinfunction "6_6") (pintype "passive"))
    )
    (net (code "221") (name "T_VU_METER_OUT_1") (class "Default")
      (node (ref "LED_OUT1") (pin "A") (pinfunction "A_A") (pintype "passive"))
      (node (ref "P8") (pin "10") (pinfunction "10_10") (pintype "passive"))
    )
    (net (code "222") (name "T_VU_METER_OUT_2") (class "Default")
      (node (ref "LED_OUT2") (pin "A") (pinfunction "A_A") (pintype "passive"))
      (node (ref "P8") (pin "9") (pinfunction "9_9") (pintype "passive"))
    )
    (net (code "223") (name "T_VU_METER_OUT_3") (class "Default")
      (node (ref "LED_OUT3") (pin "A") (pinfunction "A_A") (pintype "passive"))
      (node (ref "P8") (pin "8") (pinfunction "8_8") (pintype "passive"))
    )
    (net (code "224") (name "T_VU_METER_OUT_4") (class "Default")
      (node (ref "LED_OUT4") (pin "A") (pinfunction "A_A") (pintype "passive"))
      (node (ref "P8") (pin "7") (pinfunction "7_7") (pintype "passive"))
    )
    (net (code "225") (name "VBAT") (class "Default")
      (node (ref "U3") (pin "6") (pinfunction "VBAT_6") (pintype "power_in"))
    )
    (net (code "226") (name "VCAP_1") (class "Default")
      (node (ref "C48") (pin "2") (pinfunction "2_2") (pintype "passive"))
      (node (ref "U3") (pin "49") (pinfunction "VCAP_1_49") (pintype "power_in"))
    )
    (net (code "227") (name "VCAP_2") (class "Default")
      (node (ref "C49") (pin "2") (pinfunction "2_2") (pintype "passive"))
      (node (ref "U3") (pin "73") (pinfunction "VCAP_2_73") (pintype "power_in"))
    )
    (net (code "228") (name "VERB_POT") (class "Default")
      (node (ref "P12") (pin "10") (pinfunction "10_10") (pintype "passive"))
      (node (ref "U17") (pin "15") (pinfunction "X2_15") (pintype "bidirectional"))
    )
    (net (code "229") (name "VOCT_CV") (class "Default")
      (node (ref "C26") (pin "2") (pinfunction "2_2") (pintype "passive"))
      (node (ref "R51") (pin "2") (pinfunction "2_2") (pintype "passive"))
      (node (ref "U11") (pin "7") (pinfunction "OUT_7") (pintype "output"))
      (node (ref "U3") (pin "15") (pinfunction "PC0_15") (pintype "bidirectional"))
    )
    (net (code "230") (name "VU_METER_IN_1") (class "Default")
      (node (ref "R17") (pin "2") (pinfunction "2_2") (pintype "passive"))
      (node (ref "U3") (pin "59") (pinfunction "PD12_59") (pintype "bidirectional"))
    )
    (net (code "231") (name "VU_METER_IN_2") (class "Default")
      (node (ref "R15") (pin "2") (pinfunction "2_2") (pintype "passive"))
      (node (ref "U3") (pin "60") (pinfunction "PD13_60") (pintype "bidirectional"))
    )
    (net (code "232") (name "VU_METER_IN_3") (class "Default")
      (node (ref "R13") (pin "2") (pinfunction "2_2") (pintype "passive"))
      (node (ref "U3") (pin "61") (pinfunction "PD14_61") (pintype "bidirectional"))
    )
    (net (code "233") (name "VU_METER_IN_4") (class "Default")
      (node (ref "R12") (pin "2") (pinfunction "2_2") (pintype "passive"))
      (node (ref "U3") (pin "62") (pinfunction "PD15_62") (pintype "bidirectional"))
    )
    (net (code "234") (name "VU_METER_OUT_1") (class "Default")
      (node (ref "R10") (pin "2") (pinfunction "2_2") (pintype "passive"))
      (node (ref "U3") (pin "66") (pinfunction "PC9_66") (pintype "bidirectional"))
    )
    (net (code "235") (name "VU_METER_OUT_2") (class "Default")
      (node (ref "R8") (pin "2") (pinfunction "2_2") (pintype "passive"))
      (node (ref "U3") (pin "65") (pinfunction "PC8_65") (pintype "bidirectional"))
    )
    (net (code "236") (name "VU_METER_OUT_3") (class "Default")
      (node (ref "R7") (pin "2") (pinfunction "2_2") (pintype "passive"))
      (node (ref "U3") (pin "64") (pinfunction "PC7_64") (pintype "bidirectional"))
    )
    (net (code "237") (name "VU_METER_OUT_4") (class "Default")
      (node (ref "R5") (pin "2") (pinfunction "2_2") (pintype "passive"))
      (node (ref "U3") (pin "63") (pinfunction "PC6_63") (pintype "bidirectional"))
    )
    (net (code "238") (name "WIDTH_CV") (class "Default")
      (node (ref "C21") (pin "2") (pinfunction "2_2") (pintype "passive"))
      (node (ref "R28") (pin "2") (pinfunction "2_2") (pintype "passive"))
      (node (ref "U10") (pin "8") (pinfunction "OUT_8") (pintype "output"))
      (node (ref "U3") (pin "32") (pinfunction "PA7_32") (pintype "bidirectional"))
    )
    (net (code "239") (name "unconnected-(JP1-Pad2)") (class "Default")
      (node (ref "JP1") (pin "2") (pinfunction "2_2") (pintype "passive"))
    )
    (net (code "240") (name "unconnected-(JP1-Pad3)") (class "Default")
      (node (ref "JP1") (pin "3") (pinfunction "3_3") (pintype "passive"))
    )
    (net (code "241") (name "unconnected-(JP1-Pad6)") (class "Default")
      (node (ref "JP1") (pin "6") (pinfunction "6_6") (pintype "passive"))
    )
    (net (code "242") (name "unconnected-(J_I-LVL-PadNORM)") (class "Default")
      (node (ref "J_I-LVL") (pin "NORM") (pinfunction "NORM_NORM") (pintype "passive"))
    )
    (net (code "243") (name "unconnected-(J_LIN-PadNORM)") (class "Default")
      (node (ref "J_LIN") (pin "NORM") (pinfunction "NORM_NORM") (pintype "passive"))
    )
    (net (code "244") (name "unconnected-(J_LOUT-PadNORM)") (class "Default")
      (node (ref "J_LOUT") (pin "NORM") (pinfunction "NORM_NORM") (pintype "passive"))
    )
    (net (code "245") (name "unconnected-(J_O-LVL-PadNORM)") (class "Default")
      (node (ref "J_O-LVL") (pin "NORM") (pinfunction "NORM_NORM") (pintype "passive"))
    )
    (net (code "246") (name "unconnected-(J_ROUT-PadNORM)") (class "Default")
      (node (ref "J_ROUT") (pin "NORM") (pinfunction "NORM_NORM") (pintype "passive"))
    )
    (net (code "247") (name "unconnected-(J_VOCT-PadNORM)") (class "Default")
      (node (ref "J_VOCT") (pin "NORM") (pinfunction "NORM_NORM") (pintype "passive"))
    )
    (net (code "248") (name "unconnected-(P2-Pad7)") (class "Default")
      (node (ref "P2") (pin "7") (pinfunction "7_7") (pintype "passive"))
    )
    (net (code "249") (name "unconnected-(S_BANK-Pad2)") (class "Default")
      (node (ref "S_BANK") (pin "2") (pinfunction "2_2") (pintype "passive"))
    )
    (net (code "250") (name "unconnected-(S_BANK-Pad4)") (class "Default")
      (node (ref "S_BANK") (pin "4") (pinfunction "4_4") (pintype "passive"))
    )
    (net (code "251") (name "unconnected-(S_HOLD-Pad1)") (class "Default")
      (node (ref "S_HOLD") (pin "1") (pinfunction "1_1") (pintype "bidirectional"))
    )
    (net (code "252") (name "unconnected-(S_HOLD-Pad4)") (class "Default")
      (node (ref "S_HOLD") (pin "4") (pinfunction "4_4") (pintype "bidirectional"))
    )
    (net (code "253") (name "unconnected-(S_HOLD-Pad5)") (class "Default")
      (node (ref "S_HOLD") (pin "5") (pinfunction "5_5") (pintype "bidirectional"))
    )
    (net (code "254") (name "unconnected-(S_HOLD-Pad6)") (class "Default")
      (node (ref "S_HOLD") (pin "6") (pinfunction "6_6") (pintype "bidirectional"))
    )
    (net (code "255") (name "unconnected-(S_MUTE_INS-Pad2)") (class "Default")
      (node (ref "S_MUTE_INS") (pin "2") (pinfunction "2_2") (pintype "passive"))
    )
    (net (code "256") (name "unconnected-(S_MUTE_INS-Pad4)") (class "Default")
      (node (ref "S_MUTE_INS") (pin "4") (pinfunction "4_4") (pintype "passive"))
    )
    (net (code "257") (name "unconnected-(S_MUTE_OUTS-Pad2)") (class "Default")
      (node (ref "S_MUTE_OUTS") (pin "2") (pinfunction "2_2") (pintype "passive"))
    )
    (net (code "258") (name "unconnected-(S_MUTE_OUTS-Pad4)") (class "Default")
      (node (ref "S_MUTE_OUTS") (pin "4") (pinfunction "4_4") (pintype "passive"))
    )
    (net (code "259") (name "unconnected-(S_TIME-Pad2)") (class "Default")
      (node (ref "S_TIME") (pin "2") (pinfunction "2_2") (pintype "passive"))
    )
    (net (code "260") (name "unconnected-(S_TIME-Pad4)") (class "Default")
      (node (ref "S_TIME") (pin "4") (pinfunction "4_4") (pintype "passive"))
    )
    (net (code "261") (name "unconnected-(S_TRIG-Pad2)") (class "Default")
      (node (ref "S_TRIG") (pin "2") (pinfunction "2_2") (pintype "passive"))
    )
    (net (code "262") (name "unconnected-(S_TRIG-Pad4)") (class "Default")
      (node (ref "S_TRIG") (pin "4") (pinfunction "4_4") (pintype "passive"))
    )
    (net (code "263") (name "unconnected-(U3-PA8-Pad67)") (class "Default")
      (node (ref "U3") (pin "67") (pinfunction "PA8_67") (pintype "bidirectional"))
    )
    (net (code "264") (name "unconnected-(U3-PA11-Pad70)") (class "Default")
      (node (ref "U3") (pin "70") (pinfunction "PA11_70") (pintype "bidirectional"))
    )
    (net (code "265") (name "unconnected-(U3-PA12-Pad71)") (class "Default")
      (node (ref "U3") (pin "71") (pinfunction "PA12_71") (pintype "bidirectional"))
    )
    (net (code "266") (name "unconnected-(U3-PB2{slash}BOOT1-Pad37)") (class "Default")
      (node (ref "U3") (pin "37") (pinfunction "PB2/BOOT1_37") (pintype "bidirectional"))
    )
    (net (code "267") (name "unconnected-(U3-PB4-Pad90)") (class "Default")
      (node (ref "U3") (pin "90") (pinfunction "PB4_90") (pintype "bidirectional"))
    )
    (net (code "268") (name "unconnected-(U3-PB5-Pad91)") (class "Default")
      (node (ref "U3") (pin "91") (pinfunction "PB5_91") (pintype "bidirectional"))
    )
    (net (code "269") (name "unconnected-(U3-PB6-Pad92)") (class "Default")
      (node (ref "U3") (pin "92") (pinfunction "PB6_92") (pintype "bidirectional"))
    )
    (net (code "270") (name "unconnected-(U3-PB7-Pad93)") (class "Default")
      (node (ref "U3") (pin "93") (pinfunction "PB7_93") (pintype "bidirectional"))
    )
    (net (code "271") (name "unconnected-(U3-PB8-Pad95)") (class "Default")
      (node (ref "U3") (pin "95") (pinfunction "PB8_95") (pintype "bidirectional"))
    )
    (net (code "272") (name "unconnected-(U3-PB9-Pad96)") (class "Default")
      (node (ref "U3") (pin "96") (pinfunction "PB9_96") (pintype "bidirectional"))
    )
    (net (code "273") (name "unconnected-(U3-PC3-Pad18)") (class "Default")
      (node (ref "U3") (pin "18") (pinfunction "PC3_18") (pintype "bidirectional"))
    )
    (net (code "274") (name "unconnected-(U3-PC5-Pad34)") (class "Default")
      (node (ref "U3") (pin "34") (pinfunction "PC5_34") (pintype "bidirectional"))
    )
    (net (code "275") (name "unconnected-(U3-PC10-Pad78)") (class "Default")
      (node (ref "U3") (pin "78") (pinfunction "PC10_78") (pintype "bidirectional"))
    )
    (net (code "276") (name "unconnected-(U3-PC11-Pad79)") (class "Default")
      (node (ref "U3") (pin "79") (pinfunction "PC11_79") (pintype "bidirectional"))
    )
    (net (code "277") (name "unconnected-(U3-PC12-Pad80)") (class "Default")
      (node (ref "U3") (pin "80") (pinfunction "PC12_80") (pintype "bidirectional"))
    )
    (net (code "278") (name "unconnected-(U3-PC13-Pad7)") (class "Default")
      (node (ref "U3") (pin "7") (pinfunction "PC13_7") (pintype "bidirectional"))
    )
    (net (code "279") (name "unconnected-(U3-PC14{slash}OSC32_IN-Pad8)") (class "Default")
      (node (ref "U3") (pin "8") (pinfunction "PC14/OSC32_IN_8") (pintype "bidirectional"))
    )
    (net (code "280") (name "unconnected-(U3-PC15{slash}OSC32_OUT-Pad9)") (class "Default")
      (node (ref "U3") (pin "9") (pinfunction "PC15/OSC32_OUT_9") (pintype "bidirectional"))
    )
    (net (code "281") (name "unconnected-(U3-PD8-Pad55)") (class "Default")
      (node (ref "U3") (pin "55") (pinfunction "PD8_55") (pintype "bidirectional"))
    )
    (net (code "282") (name "unconnected-(U3-PD9-Pad56)") (class "Default")
      (node (ref "U3") (pin "56") (pinfunction "PD9_56") (pintype "bidirectional"))
    )
    (net (code "283") (name "unconnected-(U3-PD11-Pad58)") (class "Default")
      (node (ref "U3") (pin "58") (pinfunction "PD11_58") (pintype "bidirectional"))
    )
    (net (code "284") (name "unconnected-(U3-PE0-Pad97)") (class "Default")
      (node (ref "U3") (pin "97") (pinfunction "PE0_97") (pintype "bidirectional"))
    )
    (net (code "285") (name "unconnected-(U3-PE1-Pad98)") (class "Default")
      (node (ref "U3") (pin "98") (pinfunction "PE1_98") (pintype "bidirectional"))
    )
    (net (code "286") (name "unconnected-(U3-PE6-Pad5)") (class "Default")
      (node (ref "U3") (pin "5") (pinfunction "PE6_5") (pintype "bidirectional"))
    )
    (net (code "287") (name "unconnected-(U3-PE15-Pad46)") (class "Default")
      (node (ref "U3") (pin "46") (pinfunction "PE15_46") (pintype "bidirectional"))
    )
    (net (code "288") (name "unconnected-(U6-CLKOUT-Pad2)") (class "Default")
      (node (ref "U6") (pin "2") (pinfunction "CLKOUT_2") (pintype "bidirectional"))
    )
    (net (code "289") (name "unconnected-(U6-LHPOUT-Pad9)") (class "Default")
      (node (ref "U6") (pin "9") (pinfunction "LHPOUT_9") (pintype "bidirectional"))
    )
    (net (code "290") (name "unconnected-(U6-MICBIAS-Pad17)") (class "Default")
      (node (ref "U6") (pin "17") (pinfunction "MICBIAS_17") (pintype "bidirectional"))
    )
    (net (code "291") (name "unconnected-(U6-MICIN-Pad18)") (class "Default")
      (node (ref "U6") (pin "18") (pinfunction "MICIN_18") (pintype "bidirectional"))
    )
    (net (code "292") (name "unconnected-(U6-RHPOUT-Pad10)") (class "Default")
      (node (ref "U6") (pin "10") (pinfunction "RHPOUT_10") (pintype "bidirectional"))
    )
    (net (code "293") (name "unconnected-(U13B-CTRL-Pad6)") (class "Default")
      (node (ref "U13") (pin "6") (pinfunction "CTRL_6") (pintype "input"))
    )
    (net (code "294") (name "unconnected-(U13B-OUT-Pad5)") (class "Default")
      (node (ref "U13") (pin "5") (pinfunction "OUT_5") (pintype "output"))
    )
    (net (code "295") (name "unconnected-(U13C-CTRL-Pad11)") (class "Default")
      (node (ref "U13") (pin "11") (pinfunction "CTRL_11") (pintype "input"))
    )
    (net (code "296") (name "unconnected-(U13C-OUT-Pad12)") (class "Default")
      (node (ref "U13") (pin "12") (pinfunction "OUT_12") (pintype "output"))
    )
    (net (code "297") (name "unconnected-(U13E-MODE-Pad1)") (class "Default")
      (node (ref "U13") (pin "1") (pinfunction "MODE_1") (pintype "input"))
    )
    (net (code "298") (name "unconnected-(U18E-MODE-Pad1)") (class "Default")
      (node (ref "U18") (pin "1") (pinfunction "MODE_1") (pintype "input"))
    )
  )
)
